# QTouchShield.net
KiCad netlist of a schematic drawn in EAGLE
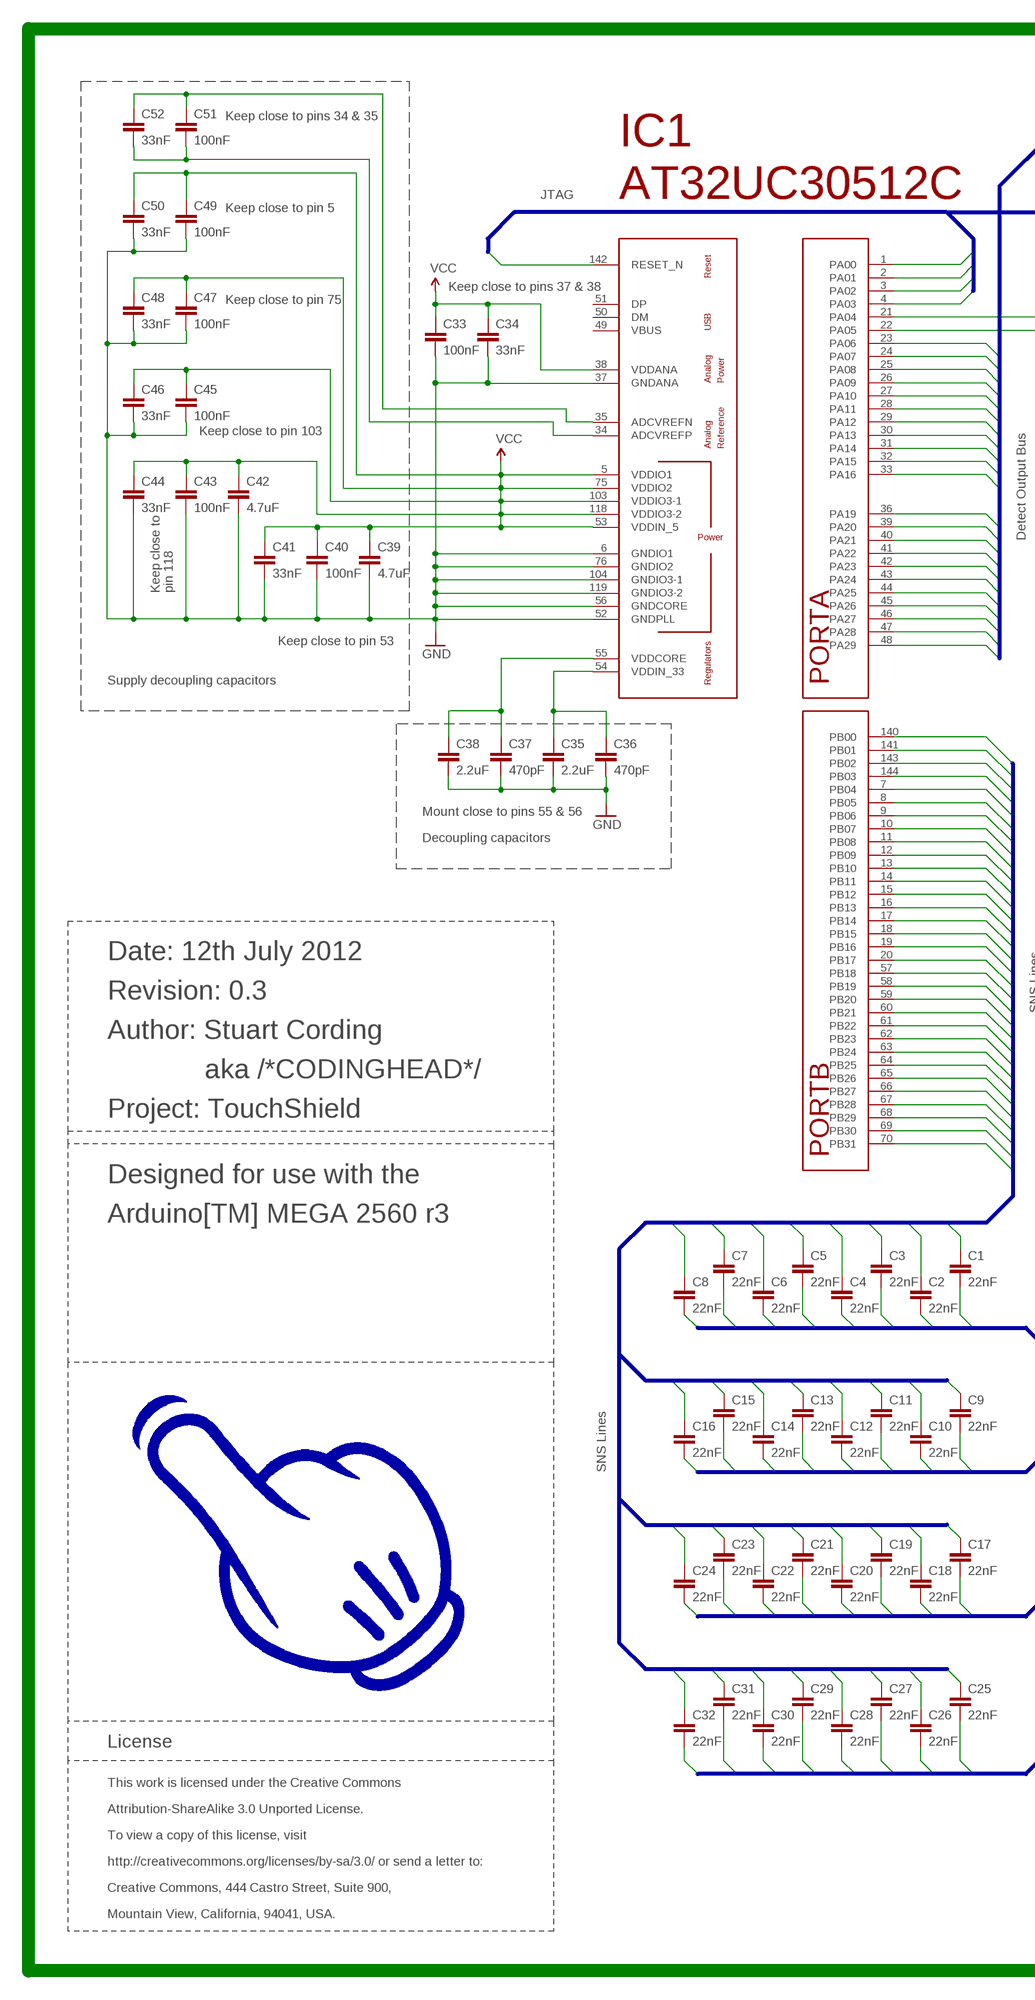
[diagram p0: schematic, sheet 1, part 1 of 2]
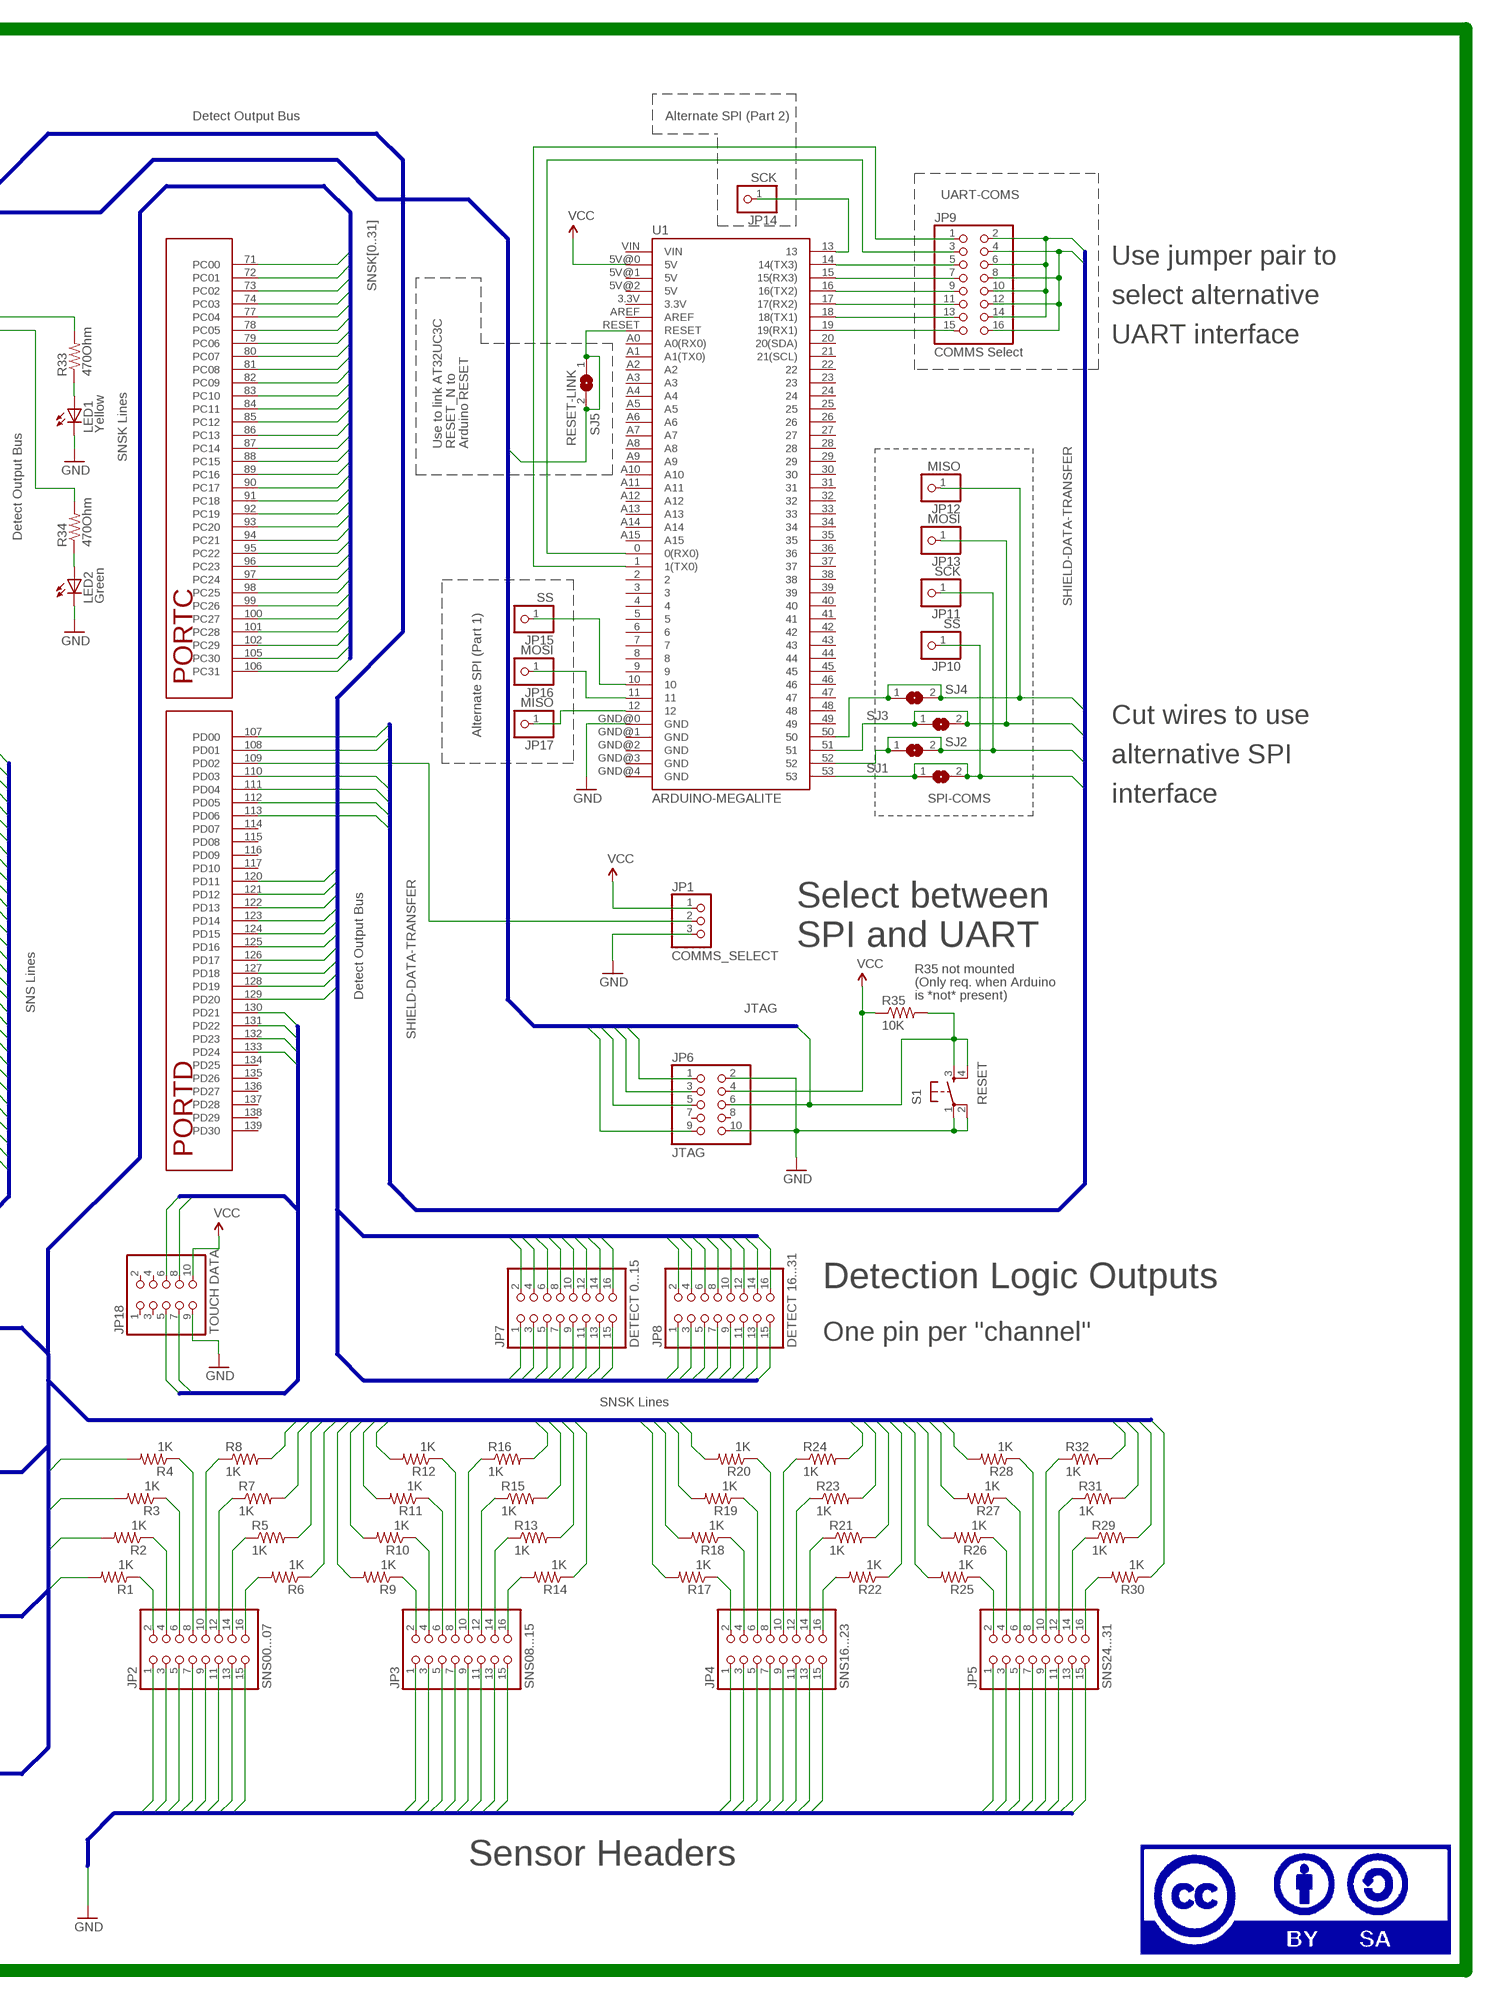
[diagram p1: schematic, sheet 1, part 2 of 2]

(export (version "E")
  (design (tool "Eeschema 10.0.6"))
  (components
    (comp (ref "C1")
      (value "22nF")
      (footprint "eagle-import:0805")
      (libsource (lib "eagle-import") (part "CAP0805"))
    )
    (comp (ref "C2")
      (value "22nF")
      (footprint "eagle-import:0805")
      (libsource (lib "eagle-import") (part "CAP0805"))
    )
    (comp (ref "C3")
      (value "22nF")
      (footprint "eagle-import:0805")
      (libsource (lib "eagle-import") (part "CAP0805"))
    )
    (comp (ref "C4")
      (value "22nF")
      (footprint "eagle-import:0805")
      (libsource (lib "eagle-import") (part "CAP0805"))
    )
    (comp (ref "C5")
      (value "22nF")
      (footprint "eagle-import:0805")
      (libsource (lib "eagle-import") (part "CAP0805"))
    )
    (comp (ref "C6")
      (value "22nF")
      (footprint "eagle-import:0805")
      (libsource (lib "eagle-import") (part "CAP0805"))
    )
    (comp (ref "C7")
      (value "22nF")
      (footprint "eagle-import:0805")
      (libsource (lib "eagle-import") (part "CAP0805"))
    )
    (comp (ref "C8")
      (value "22nF")
      (footprint "eagle-import:0805")
      (libsource (lib "eagle-import") (part "CAP0805"))
    )
    (comp (ref "C9")
      (value "22nF")
      (footprint "eagle-import:0805")
      (libsource (lib "eagle-import") (part "CAP0805"))
    )
    (comp (ref "C10")
      (value "22nF")
      (footprint "eagle-import:0805")
      (libsource (lib "eagle-import") (part "CAP0805"))
    )
    (comp (ref "C11")
      (value "22nF")
      (footprint "eagle-import:0805")
      (libsource (lib "eagle-import") (part "CAP0805"))
    )
    (comp (ref "C12")
      (value "22nF")
      (footprint "eagle-import:0805")
      (libsource (lib "eagle-import") (part "CAP0805"))
    )
    (comp (ref "C13")
      (value "22nF")
      (footprint "eagle-import:0805")
      (libsource (lib "eagle-import") (part "CAP0805"))
    )
    (comp (ref "C14")
      (value "22nF")
      (footprint "eagle-import:0805")
      (libsource (lib "eagle-import") (part "CAP0805"))
    )
    (comp (ref "C15")
      (value "22nF")
      (footprint "eagle-import:0805")
      (libsource (lib "eagle-import") (part "CAP0805"))
    )
    (comp (ref "C16")
      (value "22nF")
      (footprint "eagle-import:0805")
      (libsource (lib "eagle-import") (part "CAP0805"))
    )
    (comp (ref "C17")
      (value "22nF")
      (footprint "eagle-import:0805")
      (libsource (lib "eagle-import") (part "CAP0805"))
    )
    (comp (ref "C18")
      (value "22nF")
      (footprint "eagle-import:0805")
      (libsource (lib "eagle-import") (part "CAP0805"))
    )
    (comp (ref "C19")
      (value "22nF")
      (footprint "eagle-import:0805")
      (libsource (lib "eagle-import") (part "CAP0805"))
    )
    (comp (ref "C20")
      (value "22nF")
      (footprint "eagle-import:0805")
      (libsource (lib "eagle-import") (part "CAP0805"))
    )
    (comp (ref "C21")
      (value "22nF")
      (footprint "eagle-import:0805")
      (libsource (lib "eagle-import") (part "CAP0805"))
    )
    (comp (ref "C22")
      (value "22nF")
      (footprint "eagle-import:0805")
      (libsource (lib "eagle-import") (part "CAP0805"))
    )
    (comp (ref "C23")
      (value "22nF")
      (footprint "eagle-import:0805")
      (libsource (lib "eagle-import") (part "CAP0805"))
    )
    (comp (ref "C24")
      (value "22nF")
      (footprint "eagle-import:0805")
      (libsource (lib "eagle-import") (part "CAP0805"))
    )
    (comp (ref "C25")
      (value "22nF")
      (footprint "eagle-import:0805")
      (libsource (lib "eagle-import") (part "CAP0805"))
    )
    (comp (ref "C26")
      (value "22nF")
      (footprint "eagle-import:0805")
      (libsource (lib "eagle-import") (part "CAP0805"))
    )
    (comp (ref "C27")
      (value "22nF")
      (footprint "eagle-import:0805")
      (libsource (lib "eagle-import") (part "CAP0805"))
    )
    (comp (ref "C28")
      (value "22nF")
      (footprint "eagle-import:0805")
      (libsource (lib "eagle-import") (part "CAP0805"))
    )
    (comp (ref "C29")
      (value "22nF")
      (footprint "eagle-import:0805")
      (libsource (lib "eagle-import") (part "CAP0805"))
    )
    (comp (ref "C30")
      (value "22nF")
      (footprint "eagle-import:0805")
      (libsource (lib "eagle-import") (part "CAP0805"))
    )
    (comp (ref "C31")
      (value "22nF")
      (footprint "eagle-import:0805")
      (libsource (lib "eagle-import") (part "CAP0805"))
    )
    (comp (ref "C32")
      (value "22nF")
      (footprint "eagle-import:0805")
      (libsource (lib "eagle-import") (part "CAP0805"))
    )
    (comp (ref "C33")
      (value "100nF")
      (footprint "eagle-import:0805")
      (libsource (lib "eagle-import") (part "CAP0805"))
    )
    (comp (ref "C34")
      (value "33nF")
      (footprint "eagle-import:0805")
      (libsource (lib "eagle-import") (part "CAP0805"))
    )
    (comp (ref "C35")
      (value "2.2uF")
      (footprint "eagle-import:1210")
      (libsource (lib "eagle-import") (part "CAP1210"))
    )
    (comp (ref "C36")
      (value "470pF")
      (footprint "eagle-import:0805")
      (libsource (lib "eagle-import") (part "CAP0805"))
    )
    (comp (ref "C37")
      (value "470pF")
      (footprint "eagle-import:0805")
      (libsource (lib "eagle-import") (part "CAP0805"))
    )
    (comp (ref "C38")
      (value "2.2uF")
      (footprint "eagle-import:1210")
      (libsource (lib "eagle-import") (part "CAP1210"))
    )
    (comp (ref "C39")
      (value "4.7uF")
      (footprint "eagle-import:1210")
      (libsource (lib "eagle-import") (part "CAP1210"))
    )
    (comp (ref "C40")
      (value "100nF")
      (footprint "eagle-import:0805")
      (libsource (lib "eagle-import") (part "CAP0805"))
    )
    (comp (ref "C41")
      (value "33nF")
      (footprint "eagle-import:0805")
      (libsource (lib "eagle-import") (part "CAP0805"))
    )
    (comp (ref "C42")
      (value "4.7uF")
      (footprint "eagle-import:1210")
      (libsource (lib "eagle-import") (part "CAP1210"))
    )
    (comp (ref "C43")
      (value "100nF")
      (footprint "eagle-import:0805")
      (libsource (lib "eagle-import") (part "CAP0805"))
    )
    (comp (ref "C44")
      (value "33nF")
      (footprint "eagle-import:0805")
      (libsource (lib "eagle-import") (part "CAP0805"))
    )
    (comp (ref "C45")
      (value "100nF")
      (footprint "eagle-import:0805")
      (libsource (lib "eagle-import") (part "CAP0805"))
    )
    (comp (ref "C46")
      (value "33nF")
      (footprint "eagle-import:0805")
      (libsource (lib "eagle-import") (part "CAP0805"))
    )
    (comp (ref "C47")
      (value "100nF")
      (footprint "eagle-import:0805")
      (libsource (lib "eagle-import") (part "CAP0805"))
    )
    (comp (ref "C48")
      (value "33nF")
      (footprint "eagle-import:0805")
      (libsource (lib "eagle-import") (part "CAP0805"))
    )
    (comp (ref "C49")
      (value "100nF")
      (footprint "eagle-import:0805")
      (libsource (lib "eagle-import") (part "CAP0805"))
    )
    (comp (ref "C50")
      (value "33nF")
      (footprint "eagle-import:0805")
      (libsource (lib "eagle-import") (part "CAP0805"))
    )
    (comp (ref "C51")
      (value "100nF")
      (footprint "eagle-import:0805")
      (libsource (lib "eagle-import") (part "CAP0805"))
    )
    (comp (ref "C52")
      (value "33nF")
      (footprint "eagle-import:0805")
      (libsource (lib "eagle-import") (part "CAP0805"))
    )
    (comp (ref "IC1")
      (value "AT32UC3C0512CJEDEC-MS-026")
      (footprint "eagle-import:LQFP144")
      (libsource (lib "eagle-import") (part "AT32UC3C0512CJEDEC-MS-026"))
    )
    (comp (ref "JP1")
      (value "COMMS_SELECT")
      (footprint "eagle-import:1X03")
      (libsource (lib "eagle-import") (part "PINHD-1X3"))
    )
    (comp (ref "JP2")
      (value "SNS00...07")
      (footprint "eagle-import:2X08")
      (libsource (lib "eagle-import") (part "PINHD-2X8"))
    )
    (comp (ref "JP3")
      (value "SNS08...15")
      (footprint "eagle-import:2X08")
      (libsource (lib "eagle-import") (part "PINHD-2X8"))
    )
    (comp (ref "JP4")
      (value "SNS16...23")
      (footprint "eagle-import:2X08")
      (libsource (lib "eagle-import") (part "PINHD-2X8"))
    )
    (comp (ref "JP5")
      (value "SNS24...31")
      (footprint "eagle-import:2X08")
      (libsource (lib "eagle-import") (part "PINHD-2X8"))
    )
    (comp (ref "JP6")
      (value "JTAG")
      (footprint "eagle-import:2X05")
      (libsource (lib "eagle-import") (part "PINHD-2X5"))
    )
    (comp (ref "JP7")
      (value "DETECT 0...15")
      (footprint "eagle-import:2X08")
      (libsource (lib "eagle-import") (part "PINHD-2X8"))
    )
    (comp (ref "JP8")
      (value "DETECT 16...31")
      (footprint "eagle-import:2X08")
      (libsource (lib "eagle-import") (part "PINHD-2X8"))
    )
    (comp (ref "JP9")
      (value "COMMS Select")
      (footprint "eagle-import:2X08")
      (libsource (lib "eagle-import") (part "PINHD-2X8"))
    )
    (comp (ref "JP10")
      (value "SS")
      (footprint "eagle-import:1X01")
      (libsource (lib "eagle-import") (part "PINHD-1X1"))
    )
    (comp (ref "JP11")
      (value "SCK")
      (footprint "eagle-import:1X01")
      (libsource (lib "eagle-import") (part "PINHD-1X1"))
    )
    (comp (ref "JP12")
      (value "MISO")
      (footprint "eagle-import:1X01")
      (libsource (lib "eagle-import") (part "PINHD-1X1"))
    )
    (comp (ref "JP13")
      (value "MOSI")
      (footprint "eagle-import:1X01")
      (libsource (lib "eagle-import") (part "PINHD-1X1"))
    )
    (comp (ref "JP14")
      (value "SCK")
      (footprint "eagle-import:1X01")
      (libsource (lib "eagle-import") (part "PINHD-1X1"))
    )
    (comp (ref "JP15")
      (value "SS")
      (footprint "eagle-import:1X01")
      (libsource (lib "eagle-import") (part "PINHD-1X1"))
    )
    (comp (ref "JP16")
      (value "MOSI")
      (footprint "eagle-import:1X01")
      (libsource (lib "eagle-import") (part "PINHD-1X1"))
    )
    (comp (ref "JP17")
      (value "MISO")
      (footprint "eagle-import:1X01")
      (libsource (lib "eagle-import") (part "PINHD-1X1"))
    )
    (comp (ref "JP18")
      (value "TOUCH DATA")
      (footprint "eagle-import:2X05")
      (libsource (lib "eagle-import") (part "PINHD-2X5"))
    )
    (comp (ref "LED1")
      (value "Yellow")
      (footprint "eagle-import:LED-1206")
      (libsource (lib "eagle-import") (part "LED1206"))
    )
    (comp (ref "LED2")
      (value "Green")
      (footprint "eagle-import:LED-1206")
      (libsource (lib "eagle-import") (part "LED1206"))
    )
    (comp (ref "R1")
      (value "1K")
      (footprint "eagle-import:0805")
      (libsource (lib "eagle-import") (part "RESISTOR0805-RES"))
    )
    (comp (ref "R2")
      (value "1K")
      (footprint "eagle-import:0805")
      (libsource (lib "eagle-import") (part "RESISTOR0805-RES"))
    )
    (comp (ref "R3")
      (value "1K")
      (footprint "eagle-import:0805")
      (libsource (lib "eagle-import") (part "RESISTOR0805-RES"))
    )
    (comp (ref "R4")
      (value "1K")
      (footprint "eagle-import:0805")
      (libsource (lib "eagle-import") (part "RESISTOR0805-RES"))
    )
    (comp (ref "R5")
      (value "1K")
      (footprint "eagle-import:0805")
      (libsource (lib "eagle-import") (part "RESISTOR0805-RES"))
    )
    (comp (ref "R6")
      (value "1K")
      (footprint "eagle-import:0805")
      (libsource (lib "eagle-import") (part "RESISTOR0805-RES"))
    )
    (comp (ref "R7")
      (value "1K")
      (footprint "eagle-import:0805")
      (libsource (lib "eagle-import") (part "RESISTOR0805-RES"))
    )
    (comp (ref "R8")
      (value "1K")
      (footprint "eagle-import:0805")
      (libsource (lib "eagle-import") (part "RESISTOR0805-RES"))
    )
    (comp (ref "R9")
      (value "1K")
      (footprint "eagle-import:0805")
      (libsource (lib "eagle-import") (part "RESISTOR0805-RES"))
    )
    (comp (ref "R10")
      (value "1K")
      (footprint "eagle-import:0805")
      (libsource (lib "eagle-import") (part "RESISTOR0805-RES"))
    )
    (comp (ref "R11")
      (value "1K")
      (footprint "eagle-import:0805")
      (libsource (lib "eagle-import") (part "RESISTOR0805-RES"))
    )
    (comp (ref "R12")
      (value "1K")
      (footprint "eagle-import:0805")
      (libsource (lib "eagle-import") (part "RESISTOR0805-RES"))
    )
    (comp (ref "R13")
      (value "1K")
      (footprint "eagle-import:0805")
      (libsource (lib "eagle-import") (part "RESISTOR0805-RES"))
    )
    (comp (ref "R14")
      (value "1K")
      (footprint "eagle-import:0805")
      (libsource (lib "eagle-import") (part "RESISTOR0805-RES"))
    )
    (comp (ref "R15")
      (value "1K")
      (footprint "eagle-import:0805")
      (libsource (lib "eagle-import") (part "RESISTOR0805-RES"))
    )
    (comp (ref "R16")
      (value "1K")
      (footprint "eagle-import:0805")
      (libsource (lib "eagle-import") (part "RESISTOR0805-RES"))
    )
    (comp (ref "R17")
      (value "1K")
      (footprint "eagle-import:0805")
      (libsource (lib "eagle-import") (part "RESISTOR0805-RES"))
    )
    (comp (ref "R18")
      (value "1K")
      (footprint "eagle-import:0805")
      (libsource (lib "eagle-import") (part "RESISTOR0805-RES"))
    )
    (comp (ref "R19")
      (value "1K")
      (footprint "eagle-import:0805")
      (libsource (lib "eagle-import") (part "RESISTOR0805-RES"))
    )
    (comp (ref "R20")
      (value "1K")
      (footprint "eagle-import:0805")
      (libsource (lib "eagle-import") (part "RESISTOR0805-RES"))
    )
    (comp (ref "R21")
      (value "1K")
      (footprint "eagle-import:0805")
      (libsource (lib "eagle-import") (part "RESISTOR0805-RES"))
    )
    (comp (ref "R22")
      (value "1K")
      (footprint "eagle-import:0805")
      (libsource (lib "eagle-import") (part "RESISTOR0805-RES"))
    )
    (comp (ref "R23")
      (value "1K")
      (footprint "eagle-import:0805")
      (libsource (lib "eagle-import") (part "RESISTOR0805-RES"))
    )
    (comp (ref "R24")
      (value "1K")
      (footprint "eagle-import:0805")
      (libsource (lib "eagle-import") (part "RESISTOR0805-RES"))
    )
    (comp (ref "R25")
      (value "1K")
      (footprint "eagle-import:0805")
      (libsource (lib "eagle-import") (part "RESISTOR0805-RES"))
    )
    (comp (ref "R26")
      (value "1K")
      (footprint "eagle-import:0805")
      (libsource (lib "eagle-import") (part "RESISTOR0805-RES"))
    )
    (comp (ref "R27")
      (value "1K")
      (footprint "eagle-import:0805")
      (libsource (lib "eagle-import") (part "RESISTOR0805-RES"))
    )
    (comp (ref "R28")
      (value "1K")
      (footprint "eagle-import:0805")
      (libsource (lib "eagle-import") (part "RESISTOR0805-RES"))
    )
    (comp (ref "R29")
      (value "1K")
      (footprint "eagle-import:0805")
      (libsource (lib "eagle-import") (part "RESISTOR0805-RES"))
    )
    (comp (ref "R30")
      (value "1K")
      (footprint "eagle-import:0805")
      (libsource (lib "eagle-import") (part "RESISTOR0805-RES"))
    )
    (comp (ref "R31")
      (value "1K")
      (footprint "eagle-import:0805")
      (libsource (lib "eagle-import") (part "RESISTOR0805-RES"))
    )
    (comp (ref "R32")
      (value "1K")
      (footprint "eagle-import:0805")
      (libsource (lib "eagle-import") (part "RESISTOR0805-RES"))
    )
    (comp (ref "R33")
      (value "470Ohm")
      (footprint "eagle-import:0805")
      (libsource (lib "eagle-import") (part "RESISTOR0805-RES"))
    )
    (comp (ref "R34")
      (value "470Ohm")
      (footprint "eagle-import:0805")
      (libsource (lib "eagle-import") (part "RESISTOR0805-RES"))
    )
    (comp (ref "R35")
      (value "10K")
      (footprint "eagle-import:0805")
      (libsource (lib "eagle-import") (part "RESISTOR0805-RES"))
    )
    (comp (ref "S1")
      (value "RESET")
      (footprint "eagle-import:TACTILE_SWITCH_SMD")
      (libsource (lib "eagle-import") (part "TAC_SWITCHSMD"))
    )
    (comp (ref "SJ1") (value "SJ") (footprint "eagle-import:SJ") (libsource (lib "eagle-import") (part "SJ")))
    (comp (ref "SJ2") (value "SJ") (footprint "eagle-import:SJ") (libsource (lib "eagle-import") (part "SJ")))
    (comp (ref "SJ3") (value "SJ") (footprint "eagle-import:SJ") (libsource (lib "eagle-import") (part "SJ")))
    (comp (ref "SJ4") (value "SJ") (footprint "eagle-import:SJ") (libsource (lib "eagle-import") (part "SJ")))
    (comp (ref "SJ5")
      (value "RESET-LINK")
      (footprint "eagle-import:SJ")
      (libsource (lib "eagle-import") (part "SJ"))
    )
    (comp (ref "U1")
      (value "ARDUINO-MEGALITE")
      (footprint "eagle-import:ARDUINO_MEGA_LITE")
      (libsource (lib "eagle-import") (part "ARDUINO-MEGALITE"))
    )
  )
  (nets
    (net (code "1") (name "/JTAG_RESET") (class "Default")
      (node (ref "IC1") (pin "142") (pinfunction "RESET_N_142") (pintype "input"))
      (node (ref "JP6") (pin "6") (pinfunction "6_6") (pintype "passive"))
      (node (ref "R35") (pin "2") (pinfunction "2_2") (pintype "passive"))
      (node (ref "S1") (pin "3") (pinfunction "3_3") (pintype "passive"))
      (node (ref "S1") (pin "4") (pinfunction "4_4") (pintype "passive"))
      (node (ref "SJ5") (pin "1") (pinfunction "1_1") (pintype "passive"))
      (node (ref "SJ5") (pin "2") (pinfunction "2_2") (pintype "passive"))
      (node (ref "U1") (pin "RESET") (pinfunction "RESET_RESET") (pintype "bidirectional"))
    )
    (net (code "2") (name "/JTAG_TCK") (class "Default")
      (node (ref "IC1") (pin "1") (pinfunction "PA00_1") (pintype "bidirectional"))
      (node (ref "JP6") (pin "1") (pinfunction "1_1") (pintype "passive"))
    )
    (net (code "3") (name "/JTAG_TDI") (class "Default")
      (node (ref "IC1") (pin "2") (pinfunction "PA01_2") (pintype "bidirectional"))
      (node (ref "JP6") (pin "9") (pinfunction "9_9") (pintype "passive"))
    )
    (net (code "4") (name "/JTAG_TDO") (class "Default")
      (node (ref "IC1") (pin "3") (pinfunction "PA02_3") (pintype "bidirectional"))
      (node (ref "JP6") (pin "3") (pinfunction "3_3") (pintype "passive"))
    )
    (net (code "5") (name "/JTAG_TMS") (class "Default")
      (node (ref "IC1") (pin "4") (pinfunction "PA03_4") (pintype "bidirectional"))
      (node (ref "JP6") (pin "5") (pinfunction "5_5") (pintype "passive"))
    )
    (net (code "6") (name "/SDT-SPI0-MISO") (class "Default")
      (node (ref "IC1") (pin "112") (pinfunction "PD05_112") (pintype "bidirectional"))
      (node (ref "JP12") (pin "1") (pinfunction "1_1") (pintype "passive"))
      (node (ref "SJ4") (pin "1") (pinfunction "1_1") (pintype "passive"))
      (node (ref "SJ4") (pin "2") (pinfunction "2_2") (pintype "passive"))
      (node (ref "U1") (pin "50") (pinfunction "50_50") (pintype "bidirectional"))
    )
    (net (code "7") (name "/SDT-SPI0-MOSI") (class "Default")
      (node (ref "IC1") (pin "111") (pinfunction "PD04_111") (pintype "bidirectional"))
      (node (ref "JP13") (pin "1") (pinfunction "1_1") (pintype "passive"))
      (node (ref "SJ3") (pin "1") (pinfunction "1_1") (pintype "passive"))
      (node (ref "SJ3") (pin "2") (pinfunction "2_2") (pintype "passive"))
      (node (ref "U1") (pin "51") (pinfunction "51_51") (pintype "bidirectional"))
    )
    (net (code "8") (name "/SDT-SPI0-SCK") (class "Default")
      (node (ref "IC1") (pin "113") (pinfunction "PD06_113") (pintype "bidirectional"))
      (node (ref "JP11") (pin "1") (pinfunction "1_1") (pintype "passive"))
      (node (ref "SJ2") (pin "1") (pinfunction "1_1") (pintype "passive"))
      (node (ref "SJ2") (pin "2") (pinfunction "2_2") (pintype "passive"))
      (node (ref "U1") (pin "52") (pinfunction "52_52") (pintype "bidirectional"))
    )
    (net (code "9") (name "/SDT-SPI0-SS") (class "Default")
      (node (ref "IC1") (pin "110") (pinfunction "PD03_110") (pintype "bidirectional"))
      (node (ref "JP10") (pin "1") (pinfunction "1_1") (pintype "passive"))
      (node (ref "SJ1") (pin "1") (pinfunction "1_1") (pintype "passive"))
      (node (ref "SJ1") (pin "2") (pinfunction "2_2") (pintype "passive"))
      (node (ref "U1") (pin "53") (pinfunction "53_53") (pintype "bidirectional"))
    )
    (net (code "10") (name "/SDT-USART0-RXD") (class "Default")
      (node (ref "IC1") (pin "108") (pinfunction "PD01_108") (pintype "bidirectional"))
      (node (ref "JP9") (pin "12") (pinfunction "12_12") (pintype "passive"))
      (node (ref "JP9") (pin "16") (pinfunction "16_16") (pintype "passive"))
      (node (ref "JP9") (pin "4") (pinfunction "4_4") (pintype "passive"))
      (node (ref "JP9") (pin "8") (pinfunction "8_8") (pintype "passive"))
    )
    (net (code "11") (name "/SDT-USART0-TXD") (class "Default")
      (node (ref "IC1") (pin "107") (pinfunction "PD00_107") (pintype "bidirectional"))
      (node (ref "JP9") (pin "10") (pinfunction "10_10") (pintype "passive"))
      (node (ref "JP9") (pin "14") (pinfunction "14_14") (pintype "passive"))
      (node (ref "JP9") (pin "2") (pinfunction "2_2") (pintype "passive"))
      (node (ref "JP9") (pin "6") (pinfunction "6_6") (pintype "passive"))
    )
    (net (code "12") (name "/SHIELD-DETECT0") (class "Default")
      (node (ref "IC1") (pin "23") (pinfunction "PA06_23") (pintype "bidirectional"))
      (node (ref "JP7") (pin "1") (pinfunction "1_1") (pintype "passive"))
    )
    (net (code "13") (name "/SHIELD-DETECT1") (class "Default")
      (node (ref "IC1") (pin "24") (pinfunction "PA07_24") (pintype "bidirectional"))
      (node (ref "JP7") (pin "2") (pinfunction "2_2") (pintype "passive"))
    )
    (net (code "14") (name "/SHIELD-DETECT2") (class "Default")
      (node (ref "IC1") (pin "25") (pinfunction "PA08_25") (pintype "bidirectional"))
      (node (ref "JP7") (pin "3") (pinfunction "3_3") (pintype "passive"))
    )
    (net (code "15") (name "/SHIELD-DETECT3") (class "Default")
      (node (ref "IC1") (pin "26") (pinfunction "PA09_26") (pintype "bidirectional"))
      (node (ref "JP7") (pin "4") (pinfunction "4_4") (pintype "passive"))
    )
    (net (code "16") (name "/SHIELD-DETECT4") (class "Default")
      (node (ref "IC1") (pin "27") (pinfunction "PA10_27") (pintype "bidirectional"))
      (node (ref "JP7") (pin "5") (pinfunction "5_5") (pintype "passive"))
    )
    (net (code "17") (name "/SHIELD-DETECT5") (class "Default")
      (node (ref "IC1") (pin "28") (pinfunction "PA11_28") (pintype "bidirectional"))
      (node (ref "JP7") (pin "6") (pinfunction "6_6") (pintype "passive"))
    )
    (net (code "18") (name "/SHIELD-DETECT6") (class "Default")
      (node (ref "IC1") (pin "29") (pinfunction "PA12_29") (pintype "bidirectional"))
      (node (ref "JP7") (pin "7") (pinfunction "7_7") (pintype "passive"))
    )
    (net (code "19") (name "/SHIELD-DETECT7") (class "Default")
      (node (ref "IC1") (pin "30") (pinfunction "PA13_30") (pintype "bidirectional"))
      (node (ref "JP7") (pin "8") (pinfunction "8_8") (pintype "passive"))
    )
    (net (code "20") (name "/SHIELD-DETECT8") (class "Default")
      (node (ref "IC1") (pin "31") (pinfunction "PA14_31") (pintype "bidirectional"))
      (node (ref "JP7") (pin "9") (pinfunction "9_9") (pintype "passive"))
    )
    (net (code "21") (name "/SHIELD-DETECT9") (class "Default")
      (node (ref "IC1") (pin "32") (pinfunction "PA15_32") (pintype "bidirectional"))
      (node (ref "JP7") (pin "10") (pinfunction "10_10") (pintype "passive"))
    )
    (net (code "22") (name "/SHIELD-DETECT10") (class "Default")
      (node (ref "IC1") (pin "33") (pinfunction "PA16_33") (pintype "bidirectional"))
      (node (ref "JP7") (pin "11") (pinfunction "11_11") (pintype "passive"))
    )
    (net (code "23") (name "/SHIELD-DETECT11") (class "Default")
      (node (ref "IC1") (pin "36") (pinfunction "PA19_36") (pintype "bidirectional"))
      (node (ref "JP7") (pin "12") (pinfunction "12_12") (pintype "passive"))
    )
    (net (code "24") (name "/SHIELD-DETECT12") (class "Default")
      (node (ref "IC1") (pin "39") (pinfunction "PA20_39") (pintype "bidirectional"))
      (node (ref "JP7") (pin "13") (pinfunction "13_13") (pintype "passive"))
    )
    (net (code "25") (name "/SHIELD-DETECT13") (class "Default")
      (node (ref "IC1") (pin "40") (pinfunction "PA21_40") (pintype "bidirectional"))
      (node (ref "JP7") (pin "14") (pinfunction "14_14") (pintype "passive"))
    )
    (net (code "26") (name "/SHIELD-DETECT14") (class "Default")
      (node (ref "IC1") (pin "41") (pinfunction "PA22_41") (pintype "bidirectional"))
      (node (ref "JP7") (pin "15") (pinfunction "15_15") (pintype "passive"))
    )
    (net (code "27") (name "/SHIELD-DETECT15") (class "Default")
      (node (ref "IC1") (pin "42") (pinfunction "PA23_42") (pintype "bidirectional"))
      (node (ref "JP7") (pin "16") (pinfunction "16_16") (pintype "passive"))
    )
    (net (code "28") (name "/SHIELD-DETECT16") (class "Default")
      (node (ref "IC1") (pin "43") (pinfunction "PA24_43") (pintype "bidirectional"))
      (node (ref "JP8") (pin "1") (pinfunction "1_1") (pintype "passive"))
    )
    (net (code "29") (name "/SHIELD-DETECT17") (class "Default")
      (node (ref "IC1") (pin "44") (pinfunction "PA25_44") (pintype "bidirectional"))
      (node (ref "JP8") (pin "2") (pinfunction "2_2") (pintype "passive"))
    )
    (net (code "30") (name "/SHIELD-DETECT18") (class "Default")
      (node (ref "IC1") (pin "45") (pinfunction "PA26_45") (pintype "bidirectional"))
      (node (ref "JP8") (pin "3") (pinfunction "3_3") (pintype "passive"))
    )
    (net (code "31") (name "/SHIELD-DETECT19") (class "Default")
      (node (ref "IC1") (pin "46") (pinfunction "PA27_46") (pintype "bidirectional"))
      (node (ref "JP8") (pin "4") (pinfunction "4_4") (pintype "passive"))
    )
    (net (code "32") (name "/SHIELD-DETECT20") (class "Default")
      (node (ref "IC1") (pin "47") (pinfunction "PA28_47") (pintype "bidirectional"))
      (node (ref "JP8") (pin "5") (pinfunction "5_5") (pintype "passive"))
    )
    (net (code "33") (name "/SHIELD-DETECT21") (class "Default")
      (node (ref "IC1") (pin "48") (pinfunction "PA29_48") (pintype "bidirectional"))
      (node (ref "JP8") (pin "6") (pinfunction "6_6") (pintype "passive"))
    )
    (net (code "34") (name "/SHIELD-DETECT22") (class "Default")
      (node (ref "IC1") (pin "120") (pinfunction "PD11_120") (pintype "bidirectional"))
      (node (ref "JP8") (pin "7") (pinfunction "7_7") (pintype "passive"))
    )
    (net (code "35") (name "/SHIELD-DETECT23") (class "Default")
      (node (ref "IC1") (pin "121") (pinfunction "PD12_121") (pintype "bidirectional"))
      (node (ref "JP8") (pin "8") (pinfunction "8_8") (pintype "passive"))
    )
    (net (code "36") (name "/SHIELD-DETECT24") (class "Default")
      (node (ref "IC1") (pin "122") (pinfunction "PD13_122") (pintype "bidirectional"))
      (node (ref "JP8") (pin "9") (pinfunction "9_9") (pintype "passive"))
    )
    (net (code "37") (name "/SHIELD-DETECT25") (class "Default")
      (node (ref "IC1") (pin "123") (pinfunction "PD14_123") (pintype "bidirectional"))
      (node (ref "JP8") (pin "10") (pinfunction "10_10") (pintype "passive"))
    )
    (net (code "38") (name "/SHIELD-DETECT26") (class "Default")
      (node (ref "IC1") (pin "124") (pinfunction "PD15_124") (pintype "bidirectional"))
      (node (ref "JP8") (pin "11") (pinfunction "11_11") (pintype "passive"))
    )
    (net (code "39") (name "/SHIELD-DETECT27") (class "Default")
      (node (ref "IC1") (pin "125") (pinfunction "PD16_125") (pintype "bidirectional"))
      (node (ref "JP8") (pin "12") (pinfunction "12_12") (pintype "passive"))
    )
    (net (code "40") (name "/SHIELD-DETECT28") (class "Default")
      (node (ref "IC1") (pin "126") (pinfunction "PD17_126") (pintype "bidirectional"))
      (node (ref "JP8") (pin "13") (pinfunction "13_13") (pintype "passive"))
    )
    (net (code "41") (name "/SHIELD-DETECT29") (class "Default")
      (node (ref "IC1") (pin "127") (pinfunction "PD18_127") (pintype "bidirectional"))
      (node (ref "JP8") (pin "14") (pinfunction "14_14") (pintype "passive"))
    )
    (net (code "42") (name "/SHIELD-DETECT30") (class "Default")
      (node (ref "IC1") (pin "128") (pinfunction "PD19_128") (pintype "bidirectional"))
      (node (ref "JP8") (pin "15") (pinfunction "15_15") (pintype "passive"))
    )
    (net (code "43") (name "/SHIELD-DETECT31") (class "Default")
      (node (ref "IC1") (pin "129") (pinfunction "PD20_129") (pintype "bidirectional"))
      (node (ref "JP8") (pin "16") (pinfunction "16_16") (pintype "passive"))
    )
    (net (code "44") (name "/SNS0") (class "Default")
      (node (ref "C1") (pin "1") (pinfunction "1_1") (pintype "passive"))
      (node (ref "IC1") (pin "140") (pinfunction "PB00_140") (pintype "bidirectional"))
    )
    (net (code "45") (name "/SNS1") (class "Default")
      (node (ref "C2") (pin "1") (pinfunction "1_1") (pintype "passive"))
      (node (ref "IC1") (pin "141") (pinfunction "PB01_141") (pintype "bidirectional"))
    )
    (net (code "46") (name "/SNS2") (class "Default")
      (node (ref "C3") (pin "1") (pinfunction "1_1") (pintype "passive"))
      (node (ref "IC1") (pin "143") (pinfunction "PB02_143") (pintype "bidirectional"))
    )
    (net (code "47") (name "/SNS3") (class "Default")
      (node (ref "C4") (pin "1") (pinfunction "1_1") (pintype "passive"))
      (node (ref "IC1") (pin "144") (pinfunction "PB03_144") (pintype "bidirectional"))
    )
    (net (code "48") (name "/SNS4") (class "Default")
      (node (ref "C5") (pin "1") (pinfunction "1_1") (pintype "passive"))
      (node (ref "IC1") (pin "7") (pinfunction "PB04_7") (pintype "bidirectional"))
    )
    (net (code "49") (name "/SNS5") (class "Default")
      (node (ref "C6") (pin "1") (pinfunction "1_1") (pintype "passive"))
      (node (ref "IC1") (pin "8") (pinfunction "PB05_8") (pintype "bidirectional"))
    )
    (net (code "50") (name "/SNS6") (class "Default")
      (node (ref "C7") (pin "1") (pinfunction "1_1") (pintype "passive"))
      (node (ref "IC1") (pin "9") (pinfunction "PB06_9") (pintype "bidirectional"))
    )
    (net (code "51") (name "/SNS7") (class "Default")
      (node (ref "C8") (pin "1") (pinfunction "1_1") (pintype "passive"))
      (node (ref "IC1") (pin "10") (pinfunction "PB07_10") (pintype "bidirectional"))
    )
    (net (code "52") (name "/SNS8") (class "Default")
      (node (ref "C9") (pin "1") (pinfunction "1_1") (pintype "passive"))
      (node (ref "IC1") (pin "11") (pinfunction "PB08_11") (pintype "bidirectional"))
    )
    (net (code "53") (name "/SNS9") (class "Default")
      (node (ref "C10") (pin "1") (pinfunction "1_1") (pintype "passive"))
      (node (ref "IC1") (pin "12") (pinfunction "PB09_12") (pintype "bidirectional"))
    )
    (net (code "54") (name "/SNS10") (class "Default")
      (node (ref "C11") (pin "1") (pinfunction "1_1") (pintype "passive"))
      (node (ref "IC1") (pin "13") (pinfunction "PB10_13") (pintype "bidirectional"))
    )
    (net (code "55") (name "/SNS11") (class "Default")
      (node (ref "C12") (pin "1") (pinfunction "1_1") (pintype "passive"))
      (node (ref "IC1") (pin "14") (pinfunction "PB11_14") (pintype "bidirectional"))
    )
    (net (code "56") (name "/SNS12") (class "Default")
      (node (ref "C13") (pin "1") (pinfunction "1_1") (pintype "passive"))
      (node (ref "IC1") (pin "15") (pinfunction "PB12_15") (pintype "bidirectional"))
    )
    (net (code "57") (name "/SNS13") (class "Default")
      (node (ref "C14") (pin "1") (pinfunction "1_1") (pintype "passive"))
      (node (ref "IC1") (pin "16") (pinfunction "PB13_16") (pintype "bidirectional"))
    )
    (net (code "58") (name "/SNS14") (class "Default")
      (node (ref "C15") (pin "1") (pinfunction "1_1") (pintype "passive"))
      (node (ref "IC1") (pin "17") (pinfunction "PB14_17") (pintype "bidirectional"))
    )
    (net (code "59") (name "/SNS15") (class "Default")
      (node (ref "C16") (pin "1") (pinfunction "1_1") (pintype "passive"))
      (node (ref "IC1") (pin "18") (pinfunction "PB15_18") (pintype "bidirectional"))
    )
    (net (code "60") (name "/SNS16") (class "Default")
      (node (ref "C17") (pin "1") (pinfunction "1_1") (pintype "passive"))
      (node (ref "IC1") (pin "19") (pinfunction "PB16_19") (pintype "bidirectional"))
    )
    (net (code "61") (name "/SNS17") (class "Default")
      (node (ref "C18") (pin "1") (pinfunction "1_1") (pintype "passive"))
      (node (ref "IC1") (pin "20") (pinfunction "PB17_20") (pintype "bidirectional"))
    )
    (net (code "62") (name "/SNS18") (class "Default")
      (node (ref "C19") (pin "1") (pinfunction "1_1") (pintype "passive"))
      (node (ref "IC1") (pin "57") (pinfunction "PB18_57") (pintype "bidirectional"))
    )
    (net (code "63") (name "/SNS19") (class "Default")
      (node (ref "C20") (pin "1") (pinfunction "1_1") (pintype "passive"))
      (node (ref "IC1") (pin "58") (pinfunction "PB19_58") (pintype "bidirectional"))
    )
    (net (code "64") (name "/SNS20") (class "Default")
      (node (ref "C21") (pin "1") (pinfunction "1_1") (pintype "passive"))
      (node (ref "IC1") (pin "59") (pinfunction "PB20_59") (pintype "bidirectional"))
    )
    (net (code "65") (name "/SNS21") (class "Default")
      (node (ref "C22") (pin "1") (pinfunction "1_1") (pintype "passive"))
      (node (ref "IC1") (pin "60") (pinfunction "PB21_60") (pintype "bidirectional"))
    )
    (net (code "66") (name "/SNS22") (class "Default")
      (node (ref "C23") (pin "1") (pinfunction "1_1") (pintype "passive"))
      (node (ref "IC1") (pin "61") (pinfunction "PB22_61") (pintype "bidirectional"))
    )
    (net (code "67") (name "/SNS23") (class "Default")
      (node (ref "C24") (pin "1") (pinfunction "1_1") (pintype "passive"))
      (node (ref "IC1") (pin "62") (pinfunction "PB23_62") (pintype "bidirectional"))
    )
    (net (code "68") (name "/SNS24") (class "Default")
      (node (ref "C25") (pin "1") (pinfunction "1_1") (pintype "passive"))
      (node (ref "IC1") (pin "63") (pinfunction "PB24_63") (pintype "bidirectional"))
    )
    (net (code "69") (name "/SNS25") (class "Default")
      (node (ref "C26") (pin "1") (pinfunction "1_1") (pintype "passive"))
      (node (ref "IC1") (pin "64") (pinfunction "PB25_64") (pintype "bidirectional"))
    )
    (net (code "70") (name "/SNS26") (class "Default")
      (node (ref "C27") (pin "1") (pinfunction "1_1") (pintype "passive"))
      (node (ref "IC1") (pin "65") (pinfunction "PB26_65") (pintype "bidirectional"))
    )
    (net (code "71") (name "/SNS27") (class "Default")
      (node (ref "C28") (pin "1") (pinfunction "1_1") (pintype "passive"))
      (node (ref "IC1") (pin "66") (pinfunction "PB27_66") (pintype "bidirectional"))
    )
    (net (code "72") (name "/SNS28") (class "Default")
      (node (ref "C29") (pin "1") (pinfunction "1_1") (pintype "passive"))
      (node (ref "IC1") (pin "67") (pinfunction "PB28_67") (pintype "bidirectional"))
    )
    (net (code "73") (name "/SNS29") (class "Default")
      (node (ref "C30") (pin "1") (pinfunction "1_1") (pintype "passive"))
      (node (ref "IC1") (pin "68") (pinfunction "PB29_68") (pintype "bidirectional"))
    )
    (net (code "74") (name "/SNS30") (class "Default")
      (node (ref "C31") (pin "1") (pinfunction "1_1") (pintype "passive"))
      (node (ref "IC1") (pin "69") (pinfunction "PB30_69") (pintype "bidirectional"))
    )
    (net (code "75") (name "/SNS31") (class "Default")
      (node (ref "C32") (pin "1") (pinfunction "1_1") (pintype "passive"))
      (node (ref "IC1") (pin "70") (pinfunction "PB31_70") (pintype "bidirectional"))
    )
    (net (code "76") (name "/SNSK0") (class "Default")
      (node (ref "C1") (pin "2") (pinfunction "2_2") (pintype "passive"))
      (node (ref "IC1") (pin "71") (pinfunction "PC00_71") (pintype "bidirectional"))
      (node (ref "R1") (pin "2") (pinfunction "2_2") (pintype "passive"))
    )
    (net (code "77") (name "/SNSK1") (class "Default")
      (node (ref "C2") (pin "2") (pinfunction "2_2") (pintype "passive"))
      (node (ref "IC1") (pin "72") (pinfunction "PC01_72") (pintype "bidirectional"))
      (node (ref "R2") (pin "2") (pinfunction "2_2") (pintype "passive"))
    )
    (net (code "78") (name "/SNSK2") (class "Default")
      (node (ref "C3") (pin "2") (pinfunction "2_2") (pintype "passive"))
      (node (ref "IC1") (pin "73") (pinfunction "PC02_73") (pintype "bidirectional"))
      (node (ref "R3") (pin "2") (pinfunction "2_2") (pintype "passive"))
    )
    (net (code "79") (name "/SNSK3") (class "Default")
      (node (ref "C4") (pin "2") (pinfunction "2_2") (pintype "passive"))
      (node (ref "IC1") (pin "74") (pinfunction "PC03_74") (pintype "bidirectional"))
      (node (ref "R4") (pin "2") (pinfunction "2_2") (pintype "passive"))
    )
    (net (code "80") (name "/SNSK4") (class "Default")
      (node (ref "C5") (pin "2") (pinfunction "2_2") (pintype "passive"))
      (node (ref "IC1") (pin "77") (pinfunction "PC04_77") (pintype "bidirectional"))
      (node (ref "R8") (pin "2") (pinfunction "2_2") (pintype "passive"))
    )
    (net (code "81") (name "/SNSK5") (class "Default")
      (node (ref "C6") (pin "2") (pinfunction "2_2") (pintype "passive"))
      (node (ref "IC1") (pin "78") (pinfunction "PC05_78") (pintype "bidirectional"))
      (node (ref "R7") (pin "2") (pinfunction "2_2") (pintype "passive"))
    )
    (net (code "82") (name "/SNSK6") (class "Default")
      (node (ref "C7") (pin "2") (pinfunction "2_2") (pintype "passive"))
      (node (ref "IC1") (pin "79") (pinfunction "PC06_79") (pintype "bidirectional"))
      (node (ref "R5") (pin "2") (pinfunction "2_2") (pintype "passive"))
    )
    (net (code "83") (name "/SNSK7") (class "Default")
      (node (ref "C8") (pin "2") (pinfunction "2_2") (pintype "passive"))
      (node (ref "IC1") (pin "80") (pinfunction "PC07_80") (pintype "bidirectional"))
      (node (ref "R6") (pin "1") (pinfunction "1_1") (pintype "passive"))
    )
    (net (code "84") (name "/SNSK8") (class "Default")
      (node (ref "C9") (pin "2") (pinfunction "2_2") (pintype "passive"))
      (node (ref "IC1") (pin "81") (pinfunction "PC08_81") (pintype "bidirectional"))
      (node (ref "R9") (pin "2") (pinfunction "2_2") (pintype "passive"))
    )
    (net (code "85") (name "/SNSK9") (class "Default")
      (node (ref "C10") (pin "2") (pinfunction "2_2") (pintype "passive"))
      (node (ref "IC1") (pin "82") (pinfunction "PC09_82") (pintype "bidirectional"))
      (node (ref "R10") (pin "2") (pinfunction "2_2") (pintype "passive"))
    )
    (net (code "86") (name "/SNSK10") (class "Default")
      (node (ref "C11") (pin "2") (pinfunction "2_2") (pintype "passive"))
      (node (ref "IC1") (pin "83") (pinfunction "PC10_83") (pintype "bidirectional"))
      (node (ref "R11") (pin "2") (pinfunction "2_2") (pintype "passive"))
    )
    (net (code "87") (name "/SNSK11") (class "Default")
      (node (ref "C12") (pin "2") (pinfunction "2_2") (pintype "passive"))
      (node (ref "IC1") (pin "84") (pinfunction "PC11_84") (pintype "bidirectional"))
      (node (ref "R12") (pin "2") (pinfunction "2_2") (pintype "passive"))
    )
    (net (code "88") (name "/SNSK12") (class "Default")
      (node (ref "C13") (pin "2") (pinfunction "2_2") (pintype "passive"))
      (node (ref "IC1") (pin "85") (pinfunction "PC12_85") (pintype "bidirectional"))
      (node (ref "R16") (pin "2") (pinfunction "2_2") (pintype "passive"))
    )
    (net (code "89") (name "/SNSK13") (class "Default")
      (node (ref "C14") (pin "2") (pinfunction "2_2") (pintype "passive"))
      (node (ref "IC1") (pin "86") (pinfunction "PC13_86") (pintype "bidirectional"))
      (node (ref "R15") (pin "2") (pinfunction "2_2") (pintype "passive"))
    )
    (net (code "90") (name "/SNSK14") (class "Default")
      (node (ref "C15") (pin "2") (pinfunction "2_2") (pintype "passive"))
      (node (ref "IC1") (pin "87") (pinfunction "PC14_87") (pintype "bidirectional"))
      (node (ref "R13") (pin "2") (pinfunction "2_2") (pintype "passive"))
    )
    (net (code "91") (name "/SNSK15") (class "Default")
      (node (ref "C16") (pin "2") (pinfunction "2_2") (pintype "passive"))
      (node (ref "IC1") (pin "88") (pinfunction "PC15_88") (pintype "bidirectional"))
      (node (ref "R14") (pin "1") (pinfunction "1_1") (pintype "passive"))
    )
    (net (code "92") (name "/SNSK16") (class "Default")
      (node (ref "C17") (pin "2") (pinfunction "2_2") (pintype "passive"))
      (node (ref "IC1") (pin "89") (pinfunction "PC16_89") (pintype "bidirectional"))
      (node (ref "R17") (pin "2") (pinfunction "2_2") (pintype "passive"))
    )
    (net (code "93") (name "/SNSK17") (class "Default")
      (node (ref "C18") (pin "2") (pinfunction "2_2") (pintype "passive"))
      (node (ref "IC1") (pin "90") (pinfunction "PC17_90") (pintype "bidirectional"))
      (node (ref "R18") (pin "2") (pinfunction "2_2") (pintype "passive"))
    )
    (net (code "94") (name "/SNSK18") (class "Default")
      (node (ref "C19") (pin "2") (pinfunction "2_2") (pintype "passive"))
      (node (ref "IC1") (pin "91") (pinfunction "PC18_91") (pintype "bidirectional"))
      (node (ref "R19") (pin "2") (pinfunction "2_2") (pintype "passive"))
    )
    (net (code "95") (name "/SNSK19") (class "Default")
      (node (ref "C20") (pin "2") (pinfunction "2_2") (pintype "passive"))
      (node (ref "IC1") (pin "92") (pinfunction "PC19_92") (pintype "bidirectional"))
      (node (ref "R20") (pin "2") (pinfunction "2_2") (pintype "passive"))
    )
    (net (code "96") (name "/SNSK20") (class "Default")
      (node (ref "C21") (pin "2") (pinfunction "2_2") (pintype "passive"))
      (node (ref "IC1") (pin "93") (pinfunction "PC20_93") (pintype "bidirectional"))
      (node (ref "R24") (pin "2") (pinfunction "2_2") (pintype "passive"))
    )
    (net (code "97") (name "/SNSK21") (class "Default")
      (node (ref "C22") (pin "2") (pinfunction "2_2") (pintype "passive"))
      (node (ref "IC1") (pin "94") (pinfunction "PC21_94") (pintype "bidirectional"))
      (node (ref "R23") (pin "2") (pinfunction "2_2") (pintype "passive"))
    )
    (net (code "98") (name "/SNSK22") (class "Default")
      (node (ref "C23") (pin "2") (pinfunction "2_2") (pintype "passive"))
      (node (ref "IC1") (pin "95") (pinfunction "PC22_95") (pintype "bidirectional"))
      (node (ref "R21") (pin "2") (pinfunction "2_2") (pintype "passive"))
    )
    (net (code "99") (name "/SNSK23") (class "Default")
      (node (ref "C24") (pin "2") (pinfunction "2_2") (pintype "passive"))
      (node (ref "IC1") (pin "96") (pinfunction "PC23_96") (pintype "bidirectional"))
      (node (ref "R22") (pin "1") (pinfunction "1_1") (pintype "passive"))
    )
    (net (code "100") (name "/SNSK24") (class "Default")
      (node (ref "C25") (pin "2") (pinfunction "2_2") (pintype "passive"))
      (node (ref "IC1") (pin "97") (pinfunction "PC24_97") (pintype "bidirectional"))
      (node (ref "R25") (pin "2") (pinfunction "2_2") (pintype "passive"))
    )
    (net (code "101") (name "/SNSK25") (class "Default")
      (node (ref "C26") (pin "2") (pinfunction "2_2") (pintype "passive"))
      (node (ref "IC1") (pin "98") (pinfunction "PC25_98") (pintype "bidirectional"))
      (node (ref "R26") (pin "2") (pinfunction "2_2") (pintype "passive"))
    )
    (net (code "102") (name "/SNSK26") (class "Default")
      (node (ref "C27") (pin "2") (pinfunction "2_2") (pintype "passive"))
      (node (ref "IC1") (pin "99") (pinfunction "PC26_99") (pintype "bidirectional"))
      (node (ref "R27") (pin "2") (pinfunction "2_2") (pintype "passive"))
    )
    (net (code "103") (name "/SNSK27") (class "Default")
      (node (ref "C28") (pin "2") (pinfunction "2_2") (pintype "passive"))
      (node (ref "IC1") (pin "100") (pinfunction "PC27_100") (pintype "bidirectional"))
      (node (ref "R28") (pin "2") (pinfunction "2_2") (pintype "passive"))
    )
    (net (code "104") (name "/SNSK28") (class "Default")
      (node (ref "C29") (pin "2") (pinfunction "2_2") (pintype "passive"))
      (node (ref "IC1") (pin "101") (pinfunction "PC28_101") (pintype "bidirectional"))
      (node (ref "R32") (pin "2") (pinfunction "2_2") (pintype "passive"))
    )
    (net (code "105") (name "/SNSK29") (class "Default")
      (node (ref "C30") (pin "2") (pinfunction "2_2") (pintype "passive"))
      (node (ref "IC1") (pin "102") (pinfunction "PC29_102") (pintype "bidirectional"))
      (node (ref "R31") (pin "2") (pinfunction "2_2") (pintype "passive"))
    )
    (net (code "106") (name "/SNSK30") (class "Default")
      (node (ref "C31") (pin "2") (pinfunction "2_2") (pintype "passive"))
      (node (ref "IC1") (pin "105") (pinfunction "PC30_105") (pintype "bidirectional"))
      (node (ref "R29") (pin "2") (pinfunction "2_2") (pintype "passive"))
    )
    (net (code "107") (name "/SNSK31") (class "Default")
      (node (ref "C32") (pin "2") (pinfunction "2_2") (pintype "passive"))
      (node (ref "IC1") (pin "106") (pinfunction "PC31_106") (pintype "bidirectional"))
      (node (ref "R30") (pin "1") (pinfunction "1_1") (pintype "passive"))
    )
    (net (code "109") (name "/TOUCH_DATA-MISO") (class "Default")
      (node (ref "IC1") (pin "133") (pinfunction "PD24_133") (pintype "bidirectional"))
      (node (ref "JP18") (pin "7") (pinfunction "7_7") (pintype "passive"))
    )
    (net (code "110") (name "/TOUCH_DATA-MOSI") (class "Default")
      (node (ref "IC1") (pin "132") (pinfunction "PD23_132") (pintype "bidirectional"))
      (node (ref "JP18") (pin "6") (pinfunction "6_6") (pintype "passive"))
    )
    (net (code "111") (name "/TOUCH_DATA-SCK") (class "Default")
      (node (ref "IC1") (pin "131") (pinfunction "PD22_131") (pintype "bidirectional"))
      (node (ref "JP18") (pin "8") (pinfunction "8_8") (pintype "passive"))
    )
    (net (code "112") (name "/TOUCH_DATA-SS") (class "Default")
      (node (ref "IC1") (pin "130") (pinfunction "PD21_130") (pintype "bidirectional"))
      (node (ref "JP18") (pin "5") (pinfunction "5_5") (pintype "passive"))
    )
    (net (code "113") (name "GND") (class "Default")
      (node (ref "C33") (pin "2") (pinfunction "2_2") (pintype "passive"))
      (node (ref "C34") (pin "2") (pinfunction "2_2") (pintype "passive"))
      (node (ref "C35") (pin "2") (pinfunction "2_2") (pintype "passive"))
      (node (ref "C36") (pin "2") (pinfunction "2_2") (pintype "passive"))
      (node (ref "C37") (pin "2") (pinfunction "2_2") (pintype "passive"))
      (node (ref "C38") (pin "2") (pinfunction "2_2") (pintype "passive"))
      (node (ref "C39") (pin "2") (pinfunction "2_2") (pintype "passive"))
      (node (ref "C40") (pin "2") (pinfunction "2_2") (pintype "passive"))
      (node (ref "C41") (pin "2") (pinfunction "2_2") (pintype "passive"))
      (node (ref "C42") (pin "2") (pinfunction "2_2") (pintype "passive"))
      (node (ref "C43") (pin "2") (pinfunction "2_2") (pintype "passive"))
      (node (ref "C44") (pin "2") (pinfunction "2_2") (pintype "passive"))
      (node (ref "C45") (pin "2") (pinfunction "2_2") (pintype "passive"))
      (node (ref "C46") (pin "2") (pinfunction "2_2") (pintype "passive"))
      (node (ref "C47") (pin "2") (pinfunction "2_2") (pintype "passive"))
      (node (ref "C48") (pin "2") (pinfunction "2_2") (pintype "passive"))
      (node (ref "C49") (pin "2") (pinfunction "2_2") (pintype "passive"))
      (node (ref "C50") (pin "2") (pinfunction "2_2") (pintype "passive"))
      (node (ref "IC1") (pin "104") (pinfunction "GNDIO3-1_104") (pintype "power_in"))
      (node (ref "IC1") (pin "119") (pinfunction "GNDIO3-2_119") (pintype "power_in"))
      (node (ref "IC1") (pin "37") (pinfunction "GNDANA_37") (pintype "power_in"))
      (node (ref "IC1") (pin "52") (pinfunction "GNDPLL_52") (pintype "power_in"))
      (node (ref "IC1") (pin "56") (pinfunction "GNDCORE_56") (pintype "power_in"))
      (node (ref "IC1") (pin "6") (pinfunction "GNDIO1_6") (pintype "power_in"))
      (node (ref "IC1") (pin "76") (pinfunction "GNDIO2_76") (pintype "power_in"))
      (node (ref "JP1") (pin "3") (pinfunction "3_3") (pintype "passive"))
      (node (ref "JP18") (pin "9") (pinfunction "9_9") (pintype "passive"))
      (node (ref "JP2") (pin "1") (pinfunction "1_1") (pintype "passive"))
      (node (ref "JP2") (pin "11") (pinfunction "11_11") (pintype "passive"))
      (node (ref "JP2") (pin "13") (pinfunction "13_13") (pintype "passive"))
      (node (ref "JP2") (pin "15") (pinfunction "15_15") (pintype "passive"))
      (node (ref "JP2") (pin "3") (pinfunction "3_3") (pintype "passive"))
      (node (ref "JP2") (pin "5") (pinfunction "5_5") (pintype "passive"))
      (node (ref "JP2") (pin "7") (pinfunction "7_7") (pintype "passive"))
      (node (ref "JP2") (pin "9") (pinfunction "9_9") (pintype "passive"))
      (node (ref "JP3") (pin "1") (pinfunction "1_1") (pintype "passive"))
      (node (ref "JP3") (pin "11") (pinfunction "11_11") (pintype "passive"))
      (node (ref "JP3") (pin "13") (pinfunction "13_13") (pintype "passive"))
      (node (ref "JP3") (pin "15") (pinfunction "15_15") (pintype "passive"))
      (node (ref "JP3") (pin "3") (pinfunction "3_3") (pintype "passive"))
      (node (ref "JP3") (pin "5") (pinfunction "5_5") (pintype "passive"))
      (node (ref "JP3") (pin "7") (pinfunction "7_7") (pintype "passive"))
      (node (ref "JP3") (pin "9") (pinfunction "9_9") (pintype "passive"))
      (node (ref "JP4") (pin "1") (pinfunction "1_1") (pintype "passive"))
      (node (ref "JP4") (pin "11") (pinfunction "11_11") (pintype "passive"))
      (node (ref "JP4") (pin "13") (pinfunction "13_13") (pintype "passive"))
      (node (ref "JP4") (pin "15") (pinfunction "15_15") (pintype "passive"))
      (node (ref "JP4") (pin "3") (pinfunction "3_3") (pintype "passive"))
      (node (ref "JP4") (pin "5") (pinfunction "5_5") (pintype "passive"))
      (node (ref "JP4") (pin "7") (pinfunction "7_7") (pintype "passive"))
      (node (ref "JP4") (pin "9") (pinfunction "9_9") (pintype "passive"))
      (node (ref "JP5") (pin "1") (pinfunction "1_1") (pintype "passive"))
      (node (ref "JP5") (pin "11") (pinfunction "11_11") (pintype "passive"))
      (node (ref "JP5") (pin "13") (pinfunction "13_13") (pintype "passive"))
      (node (ref "JP5") (pin "15") (pinfunction "15_15") (pintype "passive"))
      (node (ref "JP5") (pin "3") (pinfunction "3_3") (pintype "passive"))
      (node (ref "JP5") (pin "5") (pinfunction "5_5") (pintype "passive"))
      (node (ref "JP5") (pin "7") (pinfunction "7_7") (pintype "passive"))
      (node (ref "JP5") (pin "9") (pinfunction "9_9") (pintype "passive"))
      (node (ref "JP6") (pin "10") (pinfunction "10_10") (pintype "passive"))
      (node (ref "JP6") (pin "2") (pinfunction "2_2") (pintype "passive"))
      (node (ref "LED1") (pin "C") (pinfunction "C_C") (pintype "passive"))
      (node (ref "LED2") (pin "C") (pinfunction "C_C") (pintype "passive"))
      (node (ref "S1") (pin "1") (pinfunction "1_1") (pintype "passive"))
      (node (ref "S1") (pin "2") (pinfunction "2_2") (pintype "passive"))
      (node (ref "U1") (pin "GND@0") (pinfunction "GND_GND@0") (pintype "bidirectional"))
    )
    (net (code "114") (name "Net-(IC1-ADCVREFN)") (class "Default")
      (node (ref "C51") (pin "1") (pinfunction "1_1") (pintype "passive"))
      (node (ref "C52") (pin "1") (pinfunction "1_1") (pintype "passive"))
      (node (ref "IC1") (pin "35") (pinfunction "ADCVREFN_35") (pintype "input"))
    )
    (net (code "115") (name "Net-(IC1-ADCVREFP)") (class "Default")
      (node (ref "C51") (pin "2") (pinfunction "2_2") (pintype "passive"))
      (node (ref "C52") (pin "2") (pinfunction "2_2") (pintype "passive"))
      (node (ref "IC1") (pin "34") (pinfunction "ADCVREFP_34") (pintype "input"))
    )
    (net (code "116") (name "Net-(IC1-PA04)") (class "Default")
      (node (ref "IC1") (pin "21") (pinfunction "PA04_21") (pintype "bidirectional"))
      (node (ref "R33") (pin "2") (pinfunction "2_2") (pintype "passive"))
    )
    (net (code "117") (name "Net-(IC1-PA05)") (class "Default")
      (node (ref "IC1") (pin "22") (pinfunction "PA05_22") (pintype "bidirectional"))
      (node (ref "R34") (pin "2") (pinfunction "2_2") (pintype "passive"))
    )
    (net (code "118") (name "Net-(IC1-PD02)") (class "Default")
      (node (ref "IC1") (pin "109") (pinfunction "PD02_109") (pintype "bidirectional"))
      (node (ref "JP1") (pin "2") (pinfunction "2_2") (pintype "passive"))
    )
    (net (code "119") (name "Net-(IC1-VDDCORE)") (class "Default")
      (node (ref "C37") (pin "1") (pinfunction "1_1") (pintype "passive"))
      (node (ref "C38") (pin "1") (pinfunction "1_1") (pintype "passive"))
      (node (ref "IC1") (pin "55") (pinfunction "VDDCORE_55") (pintype "power_in"))
    )
    (net (code "120") (name "Net-(IC1-VDDIN_33)") (class "Default")
      (node (ref "C35") (pin "1") (pinfunction "1_1") (pintype "passive"))
      (node (ref "C36") (pin "1") (pinfunction "1_1") (pintype "passive"))
      (node (ref "IC1") (pin "54") (pinfunction "VDDIN_33_54") (pintype "power_in"))
    )
    (net (code "121") (name "Net-(JP2-Pad2)") (class "Default")
      (node (ref "JP2") (pin "2") (pinfunction "2_2") (pintype "passive"))
      (node (ref "R1") (pin "1") (pinfunction "1_1") (pintype "passive"))
    )
    (net (code "122") (name "Net-(JP2-Pad4)") (class "Default")
      (node (ref "JP2") (pin "4") (pinfunction "4_4") (pintype "passive"))
      (node (ref "R2") (pin "1") (pinfunction "1_1") (pintype "passive"))
    )
    (net (code "123") (name "Net-(JP2-Pad6)") (class "Default")
      (node (ref "JP2") (pin "6") (pinfunction "6_6") (pintype "passive"))
      (node (ref "R3") (pin "1") (pinfunction "1_1") (pintype "passive"))
    )
    (net (code "124") (name "Net-(JP2-Pad8)") (class "Default")
      (node (ref "JP2") (pin "8") (pinfunction "8_8") (pintype "passive"))
      (node (ref "R4") (pin "1") (pinfunction "1_1") (pintype "passive"))
    )
    (net (code "125") (name "Net-(JP2-Pad10)") (class "Default")
      (node (ref "JP2") (pin "10") (pinfunction "10_10") (pintype "passive"))
      (node (ref "R8") (pin "1") (pinfunction "1_1") (pintype "passive"))
    )
    (net (code "126") (name "Net-(JP2-Pad12)") (class "Default")
      (node (ref "JP2") (pin "12") (pinfunction "12_12") (pintype "passive"))
      (node (ref "R7") (pin "1") (pinfunction "1_1") (pintype "passive"))
    )
    (net (code "127") (name "Net-(JP2-Pad14)") (class "Default")
      (node (ref "JP2") (pin "14") (pinfunction "14_14") (pintype "passive"))
      (node (ref "R5") (pin "1") (pinfunction "1_1") (pintype "passive"))
    )
    (net (code "128") (name "Net-(JP2-Pad16)") (class "Default")
      (node (ref "JP2") (pin "16") (pinfunction "16_16") (pintype "passive"))
      (node (ref "R6") (pin "2") (pinfunction "2_2") (pintype "passive"))
    )
    (net (code "129") (name "Net-(JP3-Pad2)") (class "Default")
      (node (ref "JP3") (pin "2") (pinfunction "2_2") (pintype "passive"))
      (node (ref "R9") (pin "1") (pinfunction "1_1") (pintype "passive"))
    )
    (net (code "130") (name "Net-(JP3-Pad4)") (class "Default")
      (node (ref "JP3") (pin "4") (pinfunction "4_4") (pintype "passive"))
      (node (ref "R10") (pin "1") (pinfunction "1_1") (pintype "passive"))
    )
    (net (code "131") (name "Net-(JP3-Pad6)") (class "Default")
      (node (ref "JP3") (pin "6") (pinfunction "6_6") (pintype "passive"))
      (node (ref "R11") (pin "1") (pinfunction "1_1") (pintype "passive"))
    )
    (net (code "132") (name "Net-(JP3-Pad8)") (class "Default")
      (node (ref "JP3") (pin "8") (pinfunction "8_8") (pintype "passive"))
      (node (ref "R12") (pin "1") (pinfunction "1_1") (pintype "passive"))
    )
    (net (code "133") (name "Net-(JP3-Pad10)") (class "Default")
      (node (ref "JP3") (pin "10") (pinfunction "10_10") (pintype "passive"))
      (node (ref "R16") (pin "1") (pinfunction "1_1") (pintype "passive"))
    )
    (net (code "134") (name "Net-(JP3-Pad12)") (class "Default")
      (node (ref "JP3") (pin "12") (pinfunction "12_12") (pintype "passive"))
      (node (ref "R15") (pin "1") (pinfunction "1_1") (pintype "passive"))
    )
    (net (code "135") (name "Net-(JP3-Pad14)") (class "Default")
      (node (ref "JP3") (pin "14") (pinfunction "14_14") (pintype "passive"))
      (node (ref "R13") (pin "1") (pinfunction "1_1") (pintype "passive"))
    )
    (net (code "136") (name "Net-(JP3-Pad16)") (class "Default")
      (node (ref "JP3") (pin "16") (pinfunction "16_16") (pintype "passive"))
      (node (ref "R14") (pin "2") (pinfunction "2_2") (pintype "passive"))
    )
    (net (code "137") (name "Net-(JP4-Pad2)") (class "Default")
      (node (ref "JP4") (pin "2") (pinfunction "2_2") (pintype "passive"))
      (node (ref "R17") (pin "1") (pinfunction "1_1") (pintype "passive"))
    )
    (net (code "138") (name "Net-(JP4-Pad4)") (class "Default")
      (node (ref "JP4") (pin "4") (pinfunction "4_4") (pintype "passive"))
      (node (ref "R18") (pin "1") (pinfunction "1_1") (pintype "passive"))
    )
    (net (code "139") (name "Net-(JP4-Pad6)") (class "Default")
      (node (ref "JP4") (pin "6") (pinfunction "6_6") (pintype "passive"))
      (node (ref "R19") (pin "1") (pinfunction "1_1") (pintype "passive"))
    )
    (net (code "140") (name "Net-(JP4-Pad8)") (class "Default")
      (node (ref "JP4") (pin "8") (pinfunction "8_8") (pintype "passive"))
      (node (ref "R20") (pin "1") (pinfunction "1_1") (pintype "passive"))
    )
    (net (code "141") (name "Net-(JP4-Pad10)") (class "Default")
      (node (ref "JP4") (pin "10") (pinfunction "10_10") (pintype "passive"))
      (node (ref "R24") (pin "1") (pinfunction "1_1") (pintype "passive"))
    )
    (net (code "142") (name "Net-(JP4-Pad12)") (class "Default")
      (node (ref "JP4") (pin "12") (pinfunction "12_12") (pintype "passive"))
      (node (ref "R23") (pin "1") (pinfunction "1_1") (pintype "passive"))
    )
    (net (code "143") (name "Net-(JP4-Pad14)") (class "Default")
      (node (ref "JP4") (pin "14") (pinfunction "14_14") (pintype "passive"))
      (node (ref "R21") (pin "1") (pinfunction "1_1") (pintype "passive"))
    )
    (net (code "144") (name "Net-(JP4-Pad16)") (class "Default")
      (node (ref "JP4") (pin "16") (pinfunction "16_16") (pintype "passive"))
      (node (ref "R22") (pin "2") (pinfunction "2_2") (pintype "passive"))
    )
    (net (code "145") (name "Net-(JP5-Pad2)") (class "Default")
      (node (ref "JP5") (pin "2") (pinfunction "2_2") (pintype "passive"))
      (node (ref "R25") (pin "1") (pinfunction "1_1") (pintype "passive"))
    )
    (net (code "146") (name "Net-(JP5-Pad4)") (class "Default")
      (node (ref "JP5") (pin "4") (pinfunction "4_4") (pintype "passive"))
      (node (ref "R26") (pin "1") (pinfunction "1_1") (pintype "passive"))
    )
    (net (code "147") (name "Net-(JP5-Pad6)") (class "Default")
      (node (ref "JP5") (pin "6") (pinfunction "6_6") (pintype "passive"))
      (node (ref "R27") (pin "1") (pinfunction "1_1") (pintype "passive"))
    )
    (net (code "148") (name "Net-(JP5-Pad8)") (class "Default")
      (node (ref "JP5") (pin "8") (pinfunction "8_8") (pintype "passive"))
      (node (ref "R28") (pin "1") (pinfunction "1_1") (pintype "passive"))
    )
    (net (code "149") (name "Net-(JP5-Pad10)") (class "Default")
      (node (ref "JP5") (pin "10") (pinfunction "10_10") (pintype "passive"))
      (node (ref "R32") (pin "1") (pinfunction "1_1") (pintype "passive"))
    )
    (net (code "150") (name "Net-(JP5-Pad12)") (class "Default")
      (node (ref "JP5") (pin "12") (pinfunction "12_12") (pintype "passive"))
      (node (ref "R31") (pin "1") (pinfunction "1_1") (pintype "passive"))
    )
    (net (code "151") (name "Net-(JP5-Pad14)") (class "Default")
      (node (ref "JP5") (pin "14") (pinfunction "14_14") (pintype "passive"))
      (node (ref "R29") (pin "1") (pinfunction "1_1") (pintype "passive"))
    )
    (net (code "152") (name "Net-(JP5-Pad16)") (class "Default")
      (node (ref "JP5") (pin "16") (pinfunction "16_16") (pintype "passive"))
      (node (ref "R30") (pin "2") (pinfunction "2_2") (pintype "passive"))
    )
    (net (code "153") (name "Net-(JP14-Pad1)") (class "Default")
      (node (ref "JP14") (pin "1") (pinfunction "1_1") (pintype "passive"))
      (node (ref "U1") (pin "13") (pinfunction "13_13") (pintype "bidirectional"))
    )
    (net (code "154") (name "Net-(JP15-Pad1)") (class "Default")
      (node (ref "JP15") (pin "1") (pinfunction "1_1") (pintype "passive"))
      (node (ref "U1") (pin "10") (pinfunction "10_10") (pintype "bidirectional"))
    )
    (net (code "155") (name "Net-(JP16-Pad1)") (class "Default")
      (node (ref "JP16") (pin "1") (pinfunction "1_1") (pintype "passive"))
      (node (ref "U1") (pin "11") (pinfunction "11_11") (pintype "bidirectional"))
    )
    (net (code "156") (name "Net-(JP17-Pad1)") (class "Default")
      (node (ref "JP17") (pin "1") (pinfunction "1_1") (pintype "passive"))
      (node (ref "U1") (pin "12") (pinfunction "12_12") (pintype "bidirectional"))
    )
    (net (code "157") (name "Net-(LED1-PadA)") (class "Default")
      (node (ref "LED1") (pin "A") (pinfunction "A_A") (pintype "passive"))
      (node (ref "R33") (pin "1") (pinfunction "1_1") (pintype "passive"))
    )
    (net (code "158") (name "Net-(LED2-PadA)") (class "Default")
      (node (ref "LED2") (pin "A") (pinfunction "A_A") (pintype "passive"))
      (node (ref "R34") (pin "1") (pinfunction "1_1") (pintype "passive"))
    )
    (net (code "159") (name "Net-(U1-0(RX0))") (class "Default")
      (node (ref "JP9") (pin "3") (pinfunction "3_3") (pintype "passive"))
      (node (ref "U1") (pin "0") (pinfunction "0(RX0)_0") (pintype "bidirectional"))
    )
    (net (code "160") (name "Net-(U1-1(TX0))") (class "Default")
      (node (ref "JP9") (pin "1") (pinfunction "1_1") (pintype "passive"))
      (node (ref "U1") (pin "1") (pinfunction "1(TX0)_1") (pintype "bidirectional"))
    )
    (net (code "161") (name "Net-(U1-14(TX3))") (class "Default")
      (node (ref "JP9") (pin "5") (pinfunction "5_5") (pintype "passive"))
      (node (ref "U1") (pin "14") (pinfunction "14(TX3)_14") (pintype "bidirectional"))
    )
    (net (code "162") (name "Net-(U1-15(RX3))") (class "Default")
      (node (ref "JP9") (pin "7") (pinfunction "7_7") (pintype "passive"))
      (node (ref "U1") (pin "15") (pinfunction "15(RX3)_15") (pintype "bidirectional"))
    )
    (net (code "163") (name "Net-(U1-16(TX2))") (class "Default")
      (node (ref "JP9") (pin "9") (pinfunction "9_9") (pintype "passive"))
      (node (ref "U1") (pin "16") (pinfunction "16(TX2)_16") (pintype "bidirectional"))
    )
    (net (code "164") (name "Net-(U1-17(RX2))") (class "Default")
      (node (ref "JP9") (pin "11") (pinfunction "11_11") (pintype "passive"))
      (node (ref "U1") (pin "17") (pinfunction "17(RX2)_17") (pintype "bidirectional"))
    )
    (net (code "165") (name "Net-(U1-18(TX1))") (class "Default")
      (node (ref "JP9") (pin "13") (pinfunction "13_13") (pintype "passive"))
      (node (ref "U1") (pin "18") (pinfunction "18(TX1)_18") (pintype "bidirectional"))
    )
    (net (code "166") (name "Net-(U1-19(RX1))") (class "Default")
      (node (ref "JP9") (pin "15") (pinfunction "15_15") (pintype "passive"))
      (node (ref "U1") (pin "19") (pinfunction "19(RX1)_19") (pintype "bidirectional"))
    )
    (net (code "167") (name "VCC") (class "Default")
      (node (ref "C33") (pin "1") (pinfunction "1_1") (pintype "passive"))
      (node (ref "C34") (pin "1") (pinfunction "1_1") (pintype "passive"))
      (node (ref "C39") (pin "1") (pinfunction "1_1") (pintype "passive"))
      (node (ref "C40") (pin "1") (pinfunction "1_1") (pintype "passive"))
      (node (ref "C41") (pin "1") (pinfunction "1_1") (pintype "passive"))
      (node (ref "C42") (pin "1") (pinfunction "1_1") (pintype "passive"))
      (node (ref "C43") (pin "1") (pinfunction "1_1") (pintype "passive"))
      (node (ref "C44") (pin "1") (pinfunction "1_1") (pintype "passive"))
      (node (ref "C45") (pin "1") (pinfunction "1_1") (pintype "passive"))
      (node (ref "C46") (pin "1") (pinfunction "1_1") (pintype "passive"))
      (node (ref "C47") (pin "1") (pinfunction "1_1") (pintype "passive"))
      (node (ref "C48") (pin "1") (pinfunction "1_1") (pintype "passive"))
      (node (ref "C49") (pin "1") (pinfunction "1_1") (pintype "passive"))
      (node (ref "C50") (pin "1") (pinfunction "1_1") (pintype "passive"))
      (node (ref "IC1") (pin "103") (pinfunction "VDDIO3-1_103") (pintype "power_in"))
      (node (ref "IC1") (pin "118") (pinfunction "VDDIO3-2_118") (pintype "power_in"))
      (node (ref "IC1") (pin "38") (pinfunction "VDDANA_38") (pintype "power_in"))
      (node (ref "IC1") (pin "5") (pinfunction "VDDIO1_5") (pintype "power_in"))
      (node (ref "IC1") (pin "53") (pinfunction "VDDIN_5_53") (pintype "power_in"))
      (node (ref "IC1") (pin "75") (pinfunction "VDDIO2_75") (pintype "power_in"))
      (node (ref "JP1") (pin "1") (pinfunction "1_1") (pintype "passive"))
      (node (ref "JP18") (pin "10") (pinfunction "10_10") (pintype "passive"))
      (node (ref "JP6") (pin "4") (pinfunction "4_4") (pintype "passive"))
      (node (ref "R35") (pin "1") (pinfunction "1_1") (pintype "passive"))
      (node (ref "U1") (pin "5V@0") (pinfunction "5V_5V@0") (pintype "bidirectional"))
    )
    (net (code "168") (name "unconnected-(IC1-DM-Pad50)") (class "Default")
      (node (ref "IC1") (pin "50") (pinfunction "DM_50") (pintype "bidirectional"))
    )
    (net (code "169") (name "unconnected-(IC1-DP-Pad51)") (class "Default")
      (node (ref "IC1") (pin "51") (pinfunction "DP_51") (pintype "bidirectional"))
    )
    (net (code "170") (name "unconnected-(IC1-PD07-Pad114)") (class "Default")
      (node (ref "IC1") (pin "114") (pinfunction "PD07_114") (pintype "bidirectional"))
    )
    (net (code "171") (name "unconnected-(IC1-PD08-Pad115)") (class "Default")
      (node (ref "IC1") (pin "115") (pinfunction "PD08_115") (pintype "bidirectional"))
    )
    (net (code "172") (name "unconnected-(IC1-PD09-Pad116)") (class "Default")
      (node (ref "IC1") (pin "116") (pinfunction "PD09_116") (pintype "bidirectional"))
    )
    (net (code "173") (name "unconnected-(IC1-PD10-Pad117)") (class "Default")
      (node (ref "IC1") (pin "117") (pinfunction "PD10_117") (pintype "bidirectional"))
    )
    (net (code "174") (name "unconnected-(IC1-PD25-Pad134)") (class "Default")
      (node (ref "IC1") (pin "134") (pinfunction "PD25_134") (pintype "bidirectional"))
    )
    (net (code "175") (name "unconnected-(IC1-PD26-Pad135)") (class "Default")
      (node (ref "IC1") (pin "135") (pinfunction "PD26_135") (pintype "bidirectional"))
    )
    (net (code "176") (name "unconnected-(IC1-PD27-Pad136)") (class "Default")
      (node (ref "IC1") (pin "136") (pinfunction "PD27_136") (pintype "bidirectional"))
    )
    (net (code "177") (name "unconnected-(IC1-PD28-Pad137)") (class "Default")
      (node (ref "IC1") (pin "137") (pinfunction "PD28_137") (pintype "bidirectional"))
    )
    (net (code "178") (name "unconnected-(IC1-PD29-Pad138)") (class "Default")
      (node (ref "IC1") (pin "138") (pinfunction "PD29_138") (pintype "bidirectional"))
    )
    (net (code "179") (name "unconnected-(IC1-PD30-Pad139)") (class "Default")
      (node (ref "IC1") (pin "139") (pinfunction "PD30_139") (pintype "bidirectional"))
    )
    (net (code "180") (name "unconnected-(IC1-VBUS-Pad49)") (class "Default")
      (node (ref "IC1") (pin "49") (pinfunction "VBUS_49") (pintype "input"))
    )
    (net (code "181") (name "unconnected-(JP6-Pad7)") (class "Default")
      (node (ref "JP6") (pin "7") (pinfunction "7_7") (pintype "passive"))
    )
    (net (code "182") (name "unconnected-(JP6-Pad8)") (class "Default")
      (node (ref "JP6") (pin "8") (pinfunction "8_8") (pintype "passive"))
    )
    (net (code "183") (name "unconnected-(JP18-Pad1)") (class "Default")
      (node (ref "JP18") (pin "1") (pinfunction "1_1") (pintype "passive"))
    )
    (net (code "184") (name "unconnected-(JP18-Pad2)") (class "Default")
      (node (ref "JP18") (pin "2") (pinfunction "2_2") (pintype "passive"))
    )
    (net (code "185") (name "unconnected-(JP18-Pad3)") (class "Default")
      (node (ref "JP18") (pin "3") (pinfunction "3_3") (pintype "passive"))
    )
    (net (code "186") (name "unconnected-(JP18-Pad4)") (class "Default")
      (node (ref "JP18") (pin "4") (pinfunction "4_4") (pintype "passive"))
    )
    (net (code "187") (name "unconnected-(U1-5V-Pad5V@1)") (class "Default")
      (node (ref "U1") (pin "5V@1") (pinfunction "5V_5V@1") (pintype "bidirectional"))
    )
    (net (code "188") (name "unconnected-(U1-5V-Pad5V@2)") (class "Default")
      (node (ref "U1") (pin "5V@2") (pinfunction "5V_5V@2") (pintype "bidirectional"))
    )
    (net (code "189") (name "unconnected-(U1-20(SDA)-Pad20)") (class "Default")
      (node (ref "U1") (pin "20") (pinfunction "20(SDA)_20") (pintype "bidirectional"))
    )
    (net (code "190") (name "unconnected-(U1-21(SCL)-Pad21)") (class "Default")
      (node (ref "U1") (pin "21") (pinfunction "21(SCL)_21") (pintype "bidirectional"))
    )
    (net (code "191") (name "unconnected-(U1-A0(RX0)-PadA0)") (class "Default")
      (node (ref "U1") (pin "A0") (pinfunction "A0(RX0)_A0") (pintype "bidirectional"))
    )
    (net (code "192") (name "unconnected-(U1-A1(TX0)-PadA1)") (class "Default")
      (node (ref "U1") (pin "A1") (pinfunction "A1(TX0)_A1") (pintype "bidirectional"))
    )
    (net (code "193") (name "unconnected-(U1-GND-PadGND@1)") (class "Default")
      (node (ref "U1") (pin "GND@1") (pinfunction "GND_GND@1") (pintype "bidirectional"))
    )
    (net (code "194") (name "unconnected-(U1-GND-PadGND@2)") (class "Default")
      (node (ref "U1") (pin "GND@2") (pinfunction "GND_GND@2") (pintype "bidirectional"))
    )
    (net (code "195") (name "unconnected-(U1-GND-PadGND@3)") (class "Default")
      (node (ref "U1") (pin "GND@3") (pinfunction "GND_GND@3") (pintype "bidirectional"))
    )
    (net (code "196") (name "unconnected-(U1-GND-PadGND@4)") (class "Default")
      (node (ref "U1") (pin "GND@4") (pinfunction "GND_GND@4") (pintype "bidirectional"))
    )
    (net (code "197") (name "unconnected-(U1-Pad2)") (class "Default")
      (node (ref "U1") (pin "2") (pinfunction "2_2") (pintype "bidirectional"))
    )
    (net (code "198") (name "unconnected-(U1-Pad3)") (class "Default")
      (node (ref "U1") (pin "3") (pinfunction "3_3") (pintype "bidirectional"))
    )
    (net (code "199") (name "unconnected-(U1-Pad3.3V)") (class "Default")
      (node (ref "U1") (pin "3.3V") (pinfunction "3.3V_3.3V") (pintype "bidirectional"))
    )
    (net (code "200") (name "unconnected-(U1-Pad4)") (class "Default")
      (node (ref "U1") (pin "4") (pinfunction "4_4") (pintype "bidirectional"))
    )
    (net (code "201") (name "unconnected-(U1-Pad5)") (class "Default")
      (node (ref "U1") (pin "5") (pinfunction "5_5") (pintype "bidirectional"))
    )
    (net (code "202") (name "unconnected-(U1-Pad6)") (class "Default")
      (node (ref "U1") (pin "6") (pinfunction "6_6") (pintype "bidirectional"))
    )
    (net (code "203") (name "unconnected-(U1-Pad7)") (class "Default")
      (node (ref "U1") (pin "7") (pinfunction "7_7") (pintype "bidirectional"))
    )
    (net (code "204") (name "unconnected-(U1-Pad8)") (class "Default")
      (node (ref "U1") (pin "8") (pinfunction "8_8") (pintype "bidirectional"))
    )
    (net (code "205") (name "unconnected-(U1-Pad9)") (class "Default")
      (node (ref "U1") (pin "9") (pinfunction "9_9") (pintype "bidirectional"))
    )
    (net (code "206") (name "unconnected-(U1-Pad22)") (class "Default")
      (node (ref "U1") (pin "22") (pinfunction "22_22") (pintype "bidirectional"))
    )
    (net (code "207") (name "unconnected-(U1-Pad23)") (class "Default")
      (node (ref "U1") (pin "23") (pinfunction "23_23") (pintype "bidirectional"))
    )
    (net (code "208") (name "unconnected-(U1-Pad24)") (class "Default")
      (node (ref "U1") (pin "24") (pinfunction "24_24") (pintype "bidirectional"))
    )
    (net (code "209") (name "unconnected-(U1-Pad25)") (class "Default")
      (node (ref "U1") (pin "25") (pinfunction "25_25") (pintype "bidirectional"))
    )
    (net (code "210") (name "unconnected-(U1-Pad26)") (class "Default")
      (node (ref "U1") (pin "26") (pinfunction "26_26") (pintype "bidirectional"))
    )
    (net (code "211") (name "unconnected-(U1-Pad27)") (class "Default")
      (node (ref "U1") (pin "27") (pinfunction "27_27") (pintype "bidirectional"))
    )
    (net (code "212") (name "unconnected-(U1-Pad28)") (class "Default")
      (node (ref "U1") (pin "28") (pinfunction "28_28") (pintype "bidirectional"))
    )
    (net (code "213") (name "unconnected-(U1-Pad29)") (class "Default")
      (node (ref "U1") (pin "29") (pinfunction "29_29") (pintype "bidirectional"))
    )
    (net (code "214") (name "unconnected-(U1-Pad30)") (class "Default")
      (node (ref "U1") (pin "30") (pinfunction "30_30") (pintype "bidirectional"))
    )
    (net (code "215") (name "unconnected-(U1-Pad31)") (class "Default")
      (node (ref "U1") (pin "31") (pinfunction "31_31") (pintype "bidirectional"))
    )
    (net (code "216") (name "unconnected-(U1-Pad32)") (class "Default")
      (node (ref "U1") (pin "32") (pinfunction "32_32") (pintype "bidirectional"))
    )
    (net (code "217") (name "unconnected-(U1-Pad33)") (class "Default")
      (node (ref "U1") (pin "33") (pinfunction "33_33") (pintype "bidirectional"))
    )
    (net (code "218") (name "unconnected-(U1-Pad34)") (class "Default")
      (node (ref "U1") (pin "34") (pinfunction "34_34") (pintype "bidirectional"))
    )
    (net (code "219") (name "unconnected-(U1-Pad35)") (class "Default")
      (node (ref "U1") (pin "35") (pinfunction "35_35") (pintype "bidirectional"))
    )
    (net (code "220") (name "unconnected-(U1-Pad36)") (class "Default")
      (node (ref "U1") (pin "36") (pinfunction "36_36") (pintype "bidirectional"))
    )
    (net (code "221") (name "unconnected-(U1-Pad37)") (class "Default")
      (node (ref "U1") (pin "37") (pinfunction "37_37") (pintype "bidirectional"))
    )
    (net (code "222") (name "unconnected-(U1-Pad38)") (class "Default")
      (node (ref "U1") (pin "38") (pinfunction "38_38") (pintype "bidirectional"))
    )
    (net (code "223") (name "unconnected-(U1-Pad39)") (class "Default")
      (node (ref "U1") (pin "39") (pinfunction "39_39") (pintype "bidirectional"))
    )
    (net (code "224") (name "unconnected-(U1-Pad40)") (class "Default")
      (node (ref "U1") (pin "40") (pinfunction "40_40") (pintype "bidirectional"))
    )
    (net (code "225") (name "unconnected-(U1-Pad41)") (class "Default")
      (node (ref "U1") (pin "41") (pinfunction "41_41") (pintype "bidirectional"))
    )
    (net (code "226") (name "unconnected-(U1-Pad42)") (class "Default")
      (node (ref "U1") (pin "42") (pinfunction "42_42") (pintype "bidirectional"))
    )
    (net (code "227") (name "unconnected-(U1-Pad43)") (class "Default")
      (node (ref "U1") (pin "43") (pinfunction "43_43") (pintype "bidirectional"))
    )
    (net (code "228") (name "unconnected-(U1-Pad44)") (class "Default")
      (node (ref "U1") (pin "44") (pinfunction "44_44") (pintype "bidirectional"))
    )
    (net (code "229") (name "unconnected-(U1-Pad45)") (class "Default")
      (node (ref "U1") (pin "45") (pinfunction "45_45") (pintype "bidirectional"))
    )
    (net (code "230") (name "unconnected-(U1-Pad46)") (class "Default")
      (node (ref "U1") (pin "46") (pinfunction "46_46") (pintype "bidirectional"))
    )
    (net (code "231") (name "unconnected-(U1-Pad47)") (class "Default")
      (node (ref "U1") (pin "47") (pinfunction "47_47") (pintype "bidirectional"))
    )
    (net (code "232") (name "unconnected-(U1-Pad48)") (class "Default")
      (node (ref "U1") (pin "48") (pinfunction "48_48") (pintype "bidirectional"))
    )
    (net (code "233") (name "unconnected-(U1-Pad49)") (class "Default")
      (node (ref "U1") (pin "49") (pinfunction "49_49") (pintype "bidirectional"))
    )
    (net (code "234") (name "unconnected-(U1-PadA2)") (class "Default")
      (node (ref "U1") (pin "A2") (pinfunction "A2_A2") (pintype "bidirectional"))
    )
    (net (code "235") (name "unconnected-(U1-PadA3)") (class "Default")
      (node (ref "U1") (pin "A3") (pinfunction "A3_A3") (pintype "bidirectional"))
    )
    (net (code "236") (name "unconnected-(U1-PadA4)") (class "Default")
      (node (ref "U1") (pin "A4") (pinfunction "A4_A4") (pintype "bidirectional"))
    )
    (net (code "237") (name "unconnected-(U1-PadA5)") (class "Default")
      (node (ref "U1") (pin "A5") (pinfunction "A5_A5") (pintype "bidirectional"))
    )
    (net (code "238") (name "unconnected-(U1-PadA6)") (class "Default")
      (node (ref "U1") (pin "A6") (pinfunction "A6_A6") (pintype "bidirectional"))
    )
    (net (code "239") (name "unconnected-(U1-PadA7)") (class "Default")
      (node (ref "U1") (pin "A7") (pinfunction "A7_A7") (pintype "bidirectional"))
    )
    (net (code "240") (name "unconnected-(U1-PadA8)") (class "Default")
      (node (ref "U1") (pin "A8") (pinfunction "A8_A8") (pintype "bidirectional"))
    )
    (net (code "241") (name "unconnected-(U1-PadA9)") (class "Default")
      (node (ref "U1") (pin "A9") (pinfunction "A9_A9") (pintype "bidirectional"))
    )
    (net (code "242") (name "unconnected-(U1-PadA10)") (class "Default")
      (node (ref "U1") (pin "A10") (pinfunction "A10_A10") (pintype "bidirectional"))
    )
    (net (code "243") (name "unconnected-(U1-PadA11)") (class "Default")
      (node (ref "U1") (pin "A11") (pinfunction "A11_A11") (pintype "bidirectional"))
    )
    (net (code "244") (name "unconnected-(U1-PadA12)") (class "Default")
      (node (ref "U1") (pin "A12") (pinfunction "A12_A12") (pintype "bidirectional"))
    )
    (net (code "245") (name "unconnected-(U1-PadA13)") (class "Default")
      (node (ref "U1") (pin "A13") (pinfunction "A13_A13") (pintype "bidirectional"))
    )
    (net (code "246") (name "unconnected-(U1-PadA14)") (class "Default")
      (node (ref "U1") (pin "A14") (pinfunction "A14_A14") (pintype "bidirectional"))
    )
    (net (code "247") (name "unconnected-(U1-PadA15)") (class "Default")
      (node (ref "U1") (pin "A15") (pinfunction "A15_A15") (pintype "bidirectional"))
    )
    (net (code "248") (name "unconnected-(U1-PadAREF)") (class "Default")
      (node (ref "U1") (pin "AREF") (pinfunction "AREF_AREF") (pintype "bidirectional"))
    )
    (net (code "249") (name "unconnected-(U1-PadVIN)") (class "Default")
      (node (ref "U1") (pin "VIN") (pinfunction "VIN_VIN") (pintype "bidirectional"))
    )
  )
)
